# design.net
KiCad netlist of a schematic drawn in Altium Designer
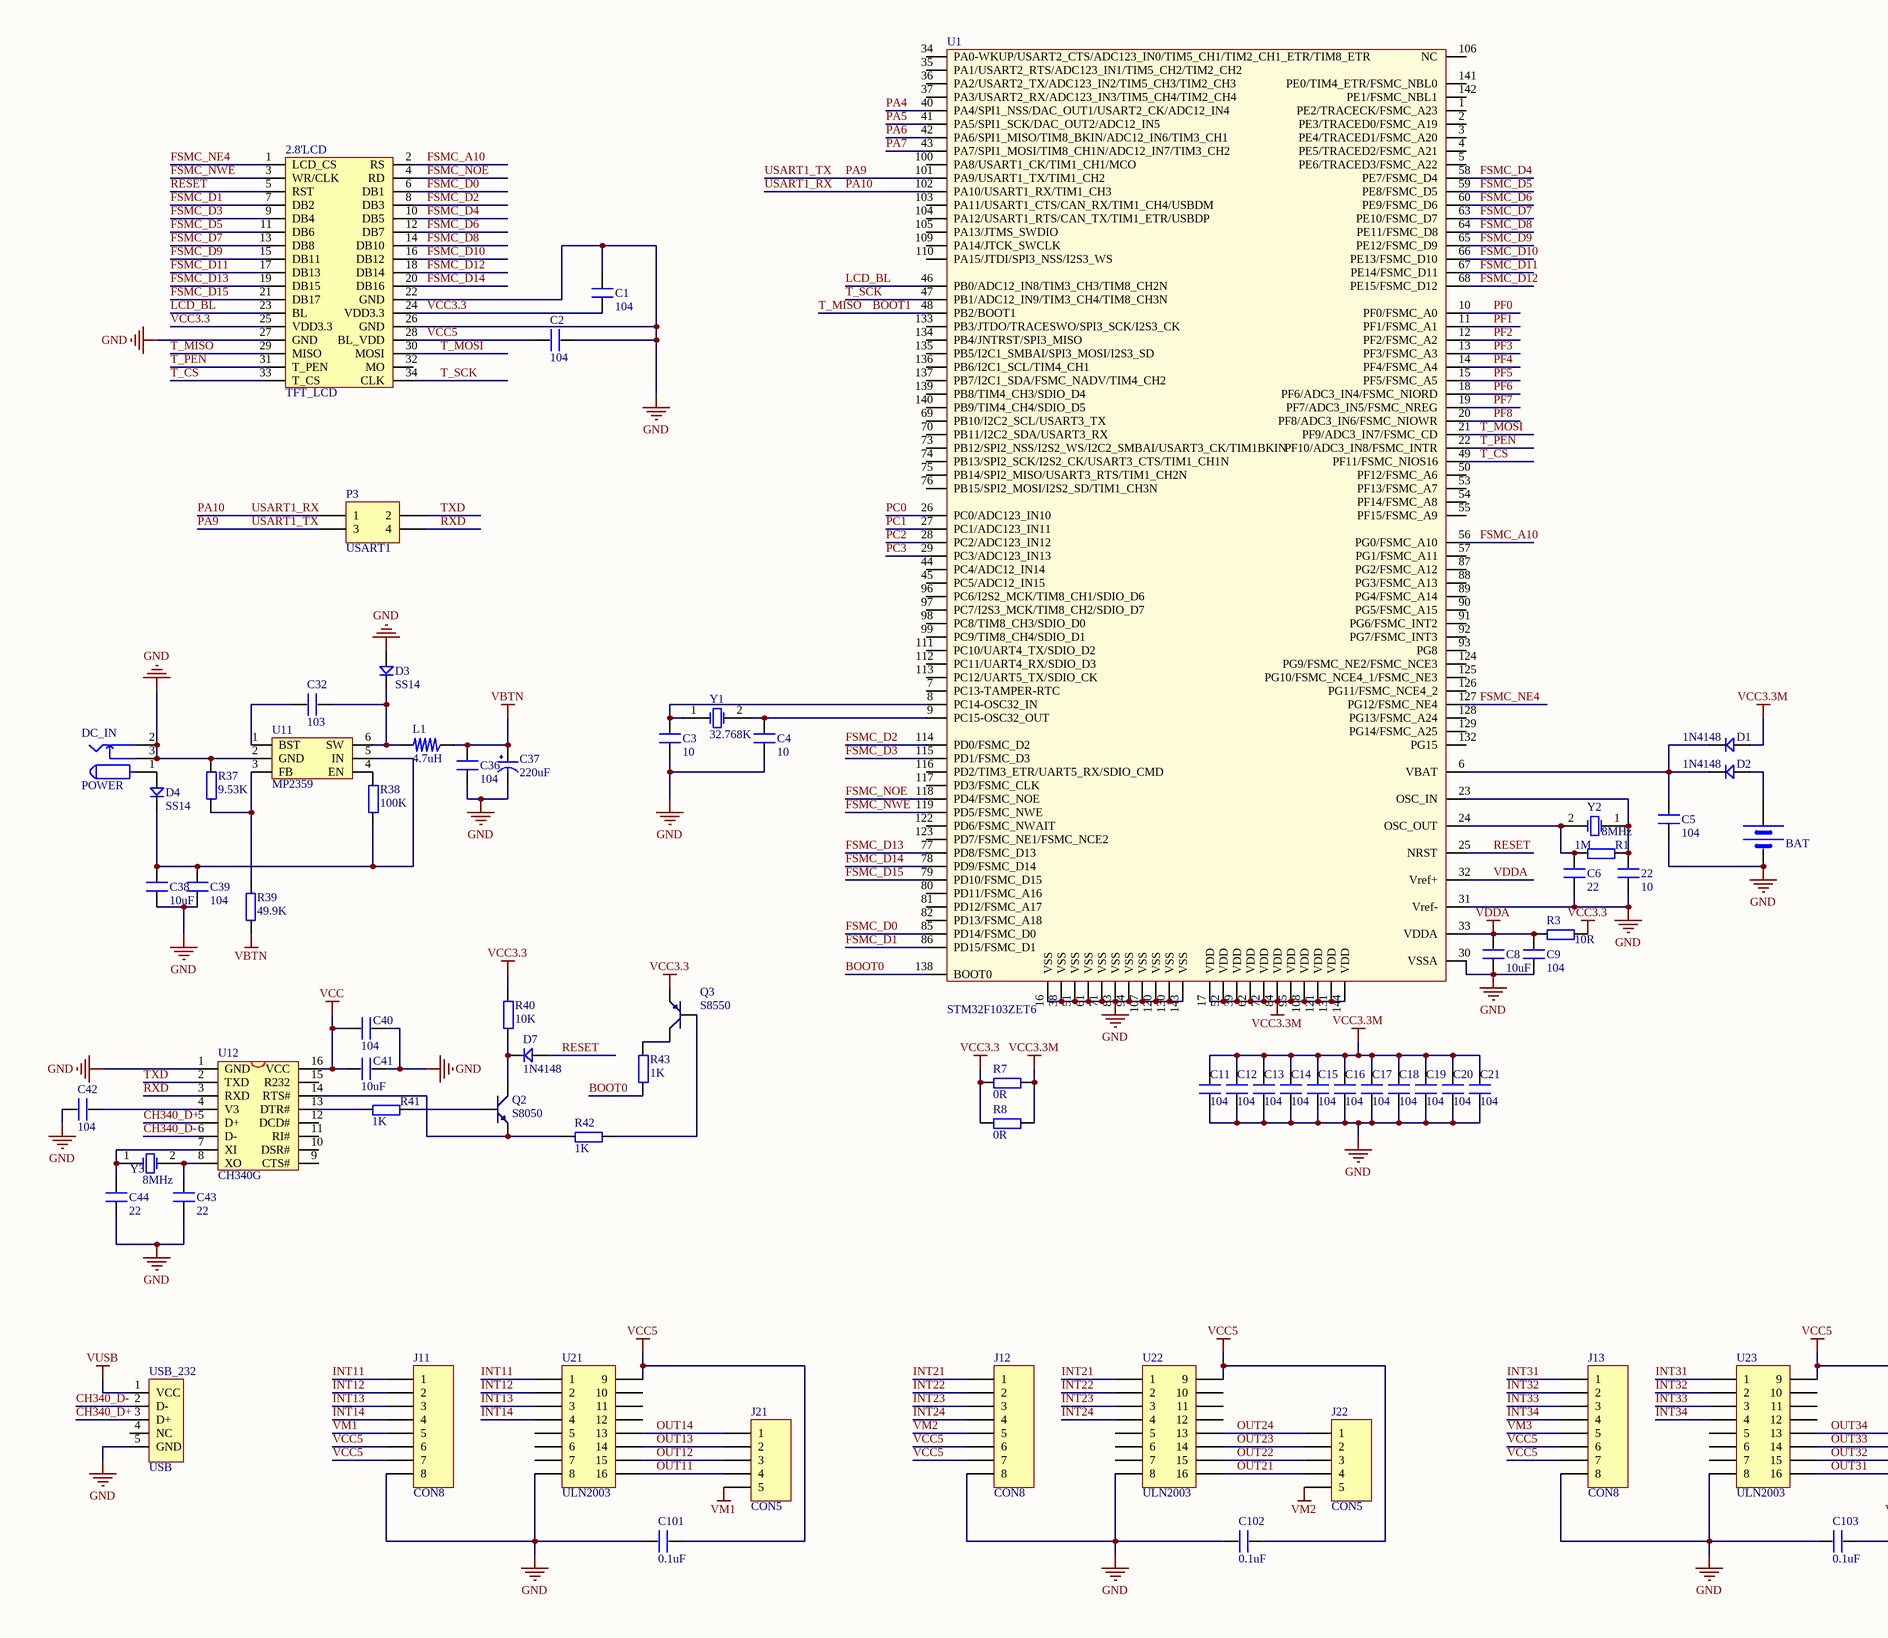
[diagram p0: 智能分类垃圾桶.SchDoc, left]
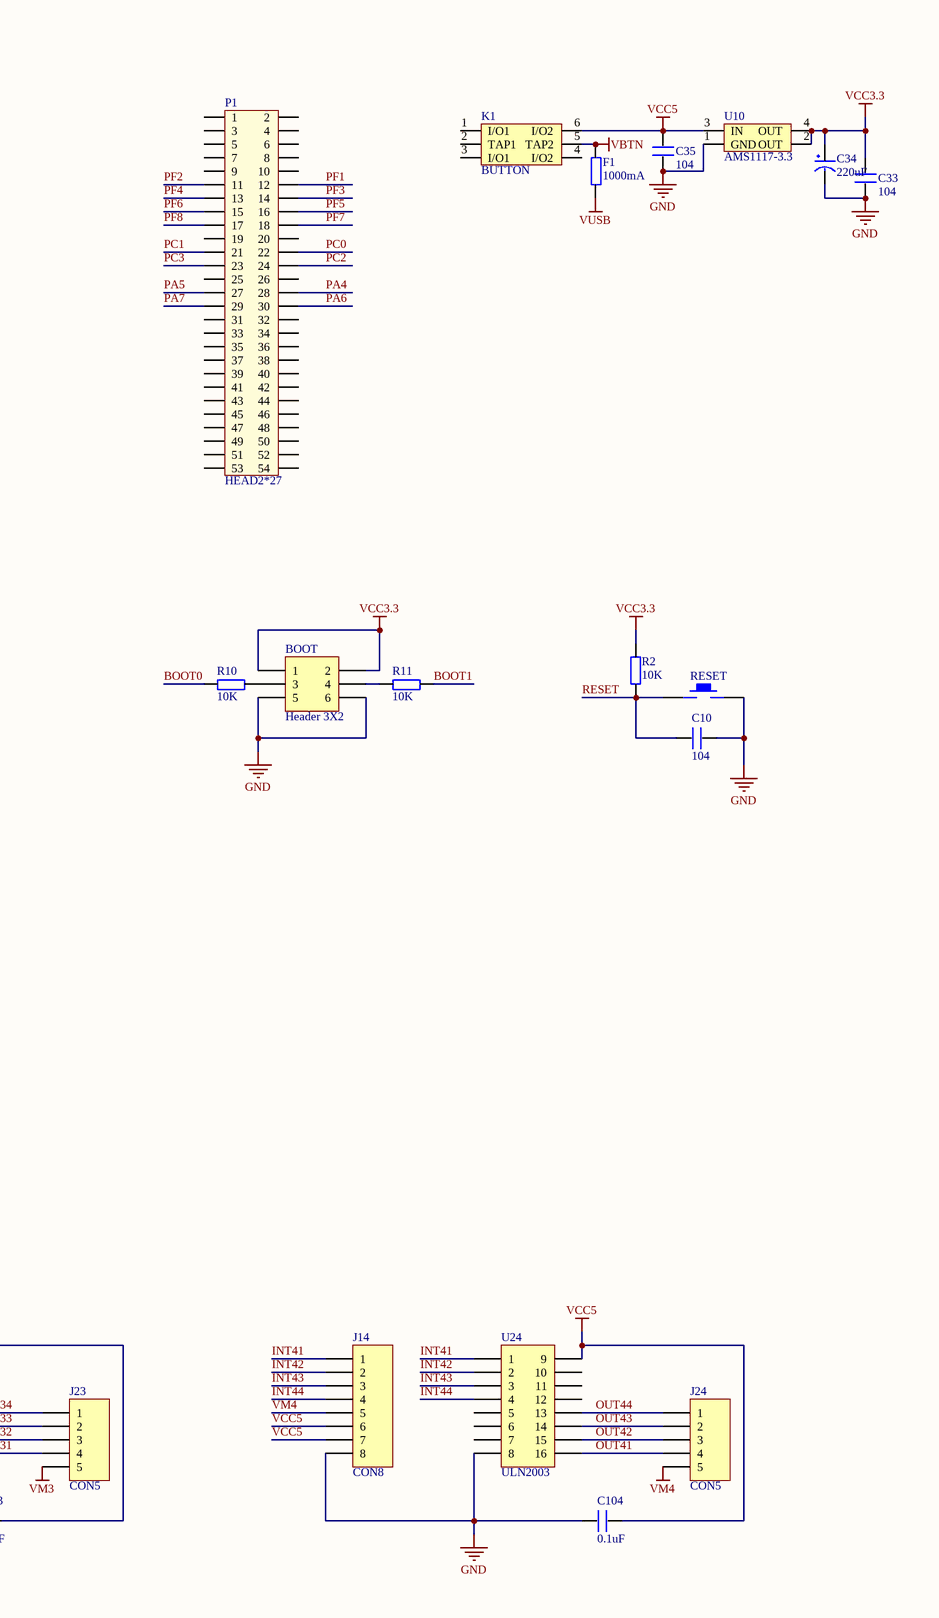
[diagram p1: 智能分类垃圾桶.SchDoc, right]

(export (version "E")
  (design (tool "Eeschema 10.0.6"))
  (components
    (comp (ref "2.8'LCD")
      (value "TFT_LCD")
      (footprint "db2*17-4.3")
      (libsource (lib "EliteSTM32封装库") (part "TFT_LCD"))
    )
    (comp (ref "22") (value "10") (footprint "0603P") (libsource (lib "EliteSTM32封装库") (part "C_1")))
    (comp (ref "BAT") (value "BATT") (footprint "BATM") (libsource (lib "EliteSTM32封装库") (part "BAT")))
    (comp (ref "BOOT")
      (value "Header 3X2")
      (footprint "HDR2X3")
      (description "Header, 3-Pin, Dual row")
      (fields (field (name "PUBLISHER") "Altium Limited"))
      (libsource (lib "EliteSTM32封装库") (part "Header 3X2"))
    )
    (comp (ref "C1") (value "104") (footprint "0603P") (libsource (lib "EliteSTM32封装库") (part "C")))
    (comp (ref "C2") (value "104") (footprint "0603P") (libsource (lib "EliteSTM32封装库") (part "C")))
    (comp (ref "C3") (value "10") (footprint "0603P") (libsource (lib "EliteSTM32封装库") (part "C_1")))
    (comp (ref "C4") (value "10") (footprint "0603P") (libsource (lib "EliteSTM32封装库") (part "C_1")))
    (comp (ref "C5") (value "104") (footprint "0603P") (libsource (lib "EliteSTM32封装库") (part "C")))
    (comp (ref "C6") (value "22") (footprint "0603P") (libsource (lib "EliteSTM32封装库") (part "C_1")))
    (comp (ref "C8") (value "10uF") (footprint "0805") (libsource (lib "EliteSTM32封装库") (part "C_2")))
    (comp (ref "C9") (value "104") (footprint "0603P") (libsource (lib "EliteSTM32封装库") (part "C")))
    (comp (ref "C10") (value "104") (footprint "0603P") (libsource (lib "EliteSTM32封装库") (part "C")))
    (comp (ref "C11") (value "104") (footprint "0603P") (libsource (lib "EliteSTM32封装库") (part "C")))
    (comp (ref "C12") (value "104") (footprint "0603P") (libsource (lib "EliteSTM32封装库") (part "C")))
    (comp (ref "C13") (value "104") (footprint "0603P") (libsource (lib "EliteSTM32封装库") (part "C")))
    (comp (ref "C14") (value "104") (footprint "0603P") (libsource (lib "EliteSTM32封装库") (part "C")))
    (comp (ref "C15") (value "104") (footprint "0603P") (libsource (lib "EliteSTM32封装库") (part "C")))
    (comp (ref "C16") (value "104") (footprint "0603P") (libsource (lib "EliteSTM32封装库") (part "C")))
    (comp (ref "C17") (value "104") (footprint "0603P") (libsource (lib "EliteSTM32封装库") (part "C")))
    (comp (ref "C18") (value "104") (footprint "0603P") (libsource (lib "EliteSTM32封装库") (part "C")))
    (comp (ref "C19") (value "104") (footprint "0603P") (libsource (lib "EliteSTM32封装库") (part "C")))
    (comp (ref "C20") (value "104") (footprint "0603P") (libsource (lib "EliteSTM32封装库") (part "C")))
    (comp (ref "C21") (value "104") (footprint "0603P") (libsource (lib "EliteSTM32封装库") (part "C")))
    (comp (ref "C32") (value "103") (footprint "0603P") (libsource (lib "EliteSTM32封装库") (part "C_3")))
    (comp (ref "C33") (value "104") (footprint "0603P") (libsource (lib "EliteSTM32封装库") (part "C")))
    (comp (ref "C34") (value "220uF") (footprint "CC6.56.5") (libsource (lib "EliteSTM32封装库") (part "CAP")))
    (comp (ref "C35") (value "104") (footprint "0603P") (libsource (lib "EliteSTM32封装库") (part "C")))
    (comp (ref "C36") (value "104") (footprint "0603P") (libsource (lib "EliteSTM32封装库") (part "C")))
    (comp (ref "C37") (value "220uF") (footprint "CC6.56.5") (libsource (lib "EliteSTM32封装库") (part "CAP")))
    (comp (ref "C38") (value "10uF") (footprint "0805") (libsource (lib "EliteSTM32封装库") (part "C_2")))
    (comp (ref "C39") (value "104") (footprint "0603P") (libsource (lib "EliteSTM32封装库") (part "C")))
    (comp (ref "C40") (value "104") (footprint "0603P") (libsource (lib "EliteSTM32封装库") (part "C")))
    (comp (ref "C41") (value "10uF") (footprint "0805") (libsource (lib "EliteSTM32封装库") (part "C_2")))
    (comp (ref "C42") (value "104") (footprint "0603P") (libsource (lib "EliteSTM32封装库") (part "C")))
    (comp (ref "C43") (value "22") (footprint "0603P") (libsource (lib "EliteSTM32封装库") (part "C_1")))
    (comp (ref "C44") (value "22") (footprint "0603P") (libsource (lib "EliteSTM32封装库") (part "C_1")))
    (comp (ref "C101") (value "0.1uF") (footprint "0805") (libsource (lib "EliteSTM32封装库") (part "C_2")))
    (comp (ref "C102") (value "0.1uF") (footprint "0805") (libsource (lib "EliteSTM32封装库") (part "C_2")))
    (comp (ref "C103") (value "0.1uF") (footprint "0805") (libsource (lib "EliteSTM32封装库") (part "C_2")))
    (comp (ref "C104") (value "0.1uF") (footprint "0805") (libsource (lib "EliteSTM32封装库") (part "C_2")))
    (comp (ref "D1") (value "1N4148") (footprint "DIODE_SOP") (libsource (lib "EliteSTM32封装库") (part "D")))
    (comp (ref "D2") (value "1N4148") (footprint "DIODE_SOP") (libsource (lib "EliteSTM32封装库") (part "D")))
    (comp (ref "D3") (value "SS14") (footprint "DIODE_SOP") (libsource (lib "EliteSTM32封装库") (part "D")))
    (comp (ref "D4") (value "SS14") (footprint "DIODE_SOP") (libsource (lib "EliteSTM32封装库") (part "D")))
    (comp (ref "D7") (value "1N4148") (footprint "DIODE_SOP") (libsource (lib "EliteSTM32封装库") (part "D")))
    (comp (ref "DC_IN") (value "POWER") (footprint "DC10B") (libsource (lib "EliteSTM32封装库") (part "POW")))
    (comp (ref "F1") (value "1000mA") (footprint "0603P") (libsource (lib "EliteSTM32封装库") (part "R")))
    (comp (ref "J11")
      (value "CON8")
      (footprint "HDR1X8")
      (description "Header, 8-Pin")
      (fields (field (name "PUBLISHER") "Altium Limited"))
      (libsource (lib "Miscellaneous Connectors") (part "Header 8"))
    )
    (comp (ref "J12")
      (value "CON8")
      (footprint "HDR1X8")
      (description "Header, 8-Pin")
      (fields (field (name "PUBLISHER") "Altium Limited"))
      (libsource (lib "Miscellaneous Connectors") (part "Header 8"))
    )
    (comp (ref "J13")
      (value "CON8")
      (footprint "HDR1X8")
      (description "Header, 8-Pin")
      (fields (field (name "PUBLISHER") "Altium Limited"))
      (libsource (lib "Miscellaneous Connectors") (part "Header 8"))
    )
    (comp (ref "J14")
      (value "CON8")
      (footprint "HDR1X8")
      (description "Header, 8-Pin")
      (fields (field (name "PUBLISHER") "Altium Limited"))
      (libsource (lib "Miscellaneous Connectors") (part "Header 8"))
    )
    (comp (ref "J21")
      (value "CON5")
      (footprint "HDR1X5")
      (description "Header, 5-Pin")
      (fields (field (name "PUBLISHER") "Altium Limited"))
      (libsource (lib "Miscellaneous Connectors") (part "Header 5"))
    )
    (comp (ref "J22")
      (value "CON5")
      (footprint "HDR1X5")
      (description "Header, 5-Pin")
      (fields (field (name "PUBLISHER") "Altium Limited"))
      (libsource (lib "Miscellaneous Connectors") (part "Header 5"))
    )
    (comp (ref "J23")
      (value "CON5")
      (footprint "HDR1X5")
      (description "Header, 5-Pin")
      (fields (field (name "PUBLISHER") "Altium Limited"))
      (libsource (lib "Miscellaneous Connectors") (part "Header 5"))
    )
    (comp (ref "J24")
      (value "CON5")
      (footprint "HDR1X5")
      (description "Header, 5-Pin")
      (fields (field (name "PUBLISHER") "Altium Limited"))
      (libsource (lib "Miscellaneous Connectors") (part "Header 5"))
    )
    (comp (ref "K1")
      (value "BUTTON")
      (footprint "BTN8.5*8.5")
      (libsource (lib "EliteSTM32封装库") (part "BUTTON"))
    )
    (comp (ref "L1") (value "4.7uH") (footprint "L_SOP74") (libsource (lib "EliteSTM32封装库") (part "L_SOP")))
    (comp (ref "P1")
      (value "HEAD2*27")
      (footprint "HEAD2*27")
      (libsource (lib "EliteSTM32封装库") (part "HEAD2*27"))
    )
    (comp (ref "P3")
      (value "USART1")
      (footprint "HDR2X2")
      (description "Header, 2-Pin, Dual row")
      (fields (field (name "PUBLISHER") "Altium Limited"))
      (libsource (lib "EliteSTM32封装库") (part "Header 2X2"))
    )
    (comp (ref "Q2")
      (value "S8050")
      (footprint "SOT-23R")
      (description "8050/BCW846/BCW847")
      (libsource (lib "EliteSTM32封装库") (part "NPN"))
    )
    (comp (ref "Q3")
      (value "S8550")
      (footprint "SOT-23R")
      (description "8550/BCW68")
      (libsource (lib "EliteSTM32封装库") (part "PNP"))
    )
    (comp (ref "R1") (value "1M") (footprint "0603P") (libsource (lib "EliteSTM32封装库") (part "R")))
    (comp (ref "R2") (value "10K") (footprint "0603P") (libsource (lib "EliteSTM32封装库") (part "R")))
    (comp (ref "R3") (value "10R") (footprint "0603P") (libsource (lib "EliteSTM32封装库") (part "R_1")))
    (comp (ref "R7") (value "0R") (footprint "0603P") (libsource (lib "EliteSTM32封装库") (part "R_2")))
    (comp (ref "R8") (value "0R") (footprint "0603P") (libsource (lib "EliteSTM32封装库") (part "R_2")))
    (comp (ref "R10") (value "10K") (footprint "0603P") (libsource (lib "EliteSTM32封装库") (part "R")))
    (comp (ref "R11") (value "10K") (footprint "0603P") (libsource (lib "EliteSTM32封装库") (part "R")))
    (comp (ref "R37") (value "9.53K") (footprint "0603P") (libsource (lib "EliteSTM32封装库") (part "R")))
    (comp (ref "R38") (value "100K") (footprint "0603P") (libsource (lib "EliteSTM32封装库") (part "R")))
    (comp (ref "R39") (value "49.9K") (footprint "0603P") (libsource (lib "EliteSTM32封装库") (part "R")))
    (comp (ref "R40") (value "10K") (footprint "0603P") (libsource (lib "EliteSTM32封装库") (part "R")))
    (comp (ref "R41") (value "1K") (footprint "0603P") (libsource (lib "EliteSTM32封装库") (part "R")))
    (comp (ref "R42") (value "1K") (footprint "0603P") (libsource (lib "EliteSTM32封装库") (part "R")))
    (comp (ref "R43") (value "1K") (footprint "0603P") (libsource (lib "EliteSTM32封装库") (part "R")))
    (comp (ref "RESET") (value "KEY_M") (footprint "KEY_M") (libsource (lib "EliteSTM32封装库") (part "KEY_M")))
    (comp (ref "U1")
      (value "STM32F103ZET6")
      (footprint "LQFP144")
      (libsource (lib "EliteSTM32封装库") (part "STM32F103ZET6"))
    )
    (comp (ref "U10")
      (value "AMS1117-3.3")
      (footprint "AMS1117")
      (libsource (lib "EliteSTM32封装库") (part "AMS1117"))
    )
    (comp (ref "U11")
      (value "MP2359")
      (footprint "SOT-23-6")
      (description "DC DC Step Down IC")
      (libsource (lib "EliteSTM32封装库") (part "MP2359"))
    )
    (comp (ref "U12")
      (value "CH340G")
      (footprint "SOP16M")
      (description "USB2UART")
      (libsource (lib "EliteSTM32封装库") (part "CH340G"))
    )
    (comp (ref "U21")
      (value "ULN2003")
      (footprint "SOP16M")
      (description "Header, 8-Pin, Dual row")
      (fields (field (name "PUBLISHER") "Altium Limited"))
      (libsource (lib "Miscellaneous Connectors") (part "Header 8X2A"))
    )
    (comp (ref "U22")
      (value "ULN2003")
      (footprint "SOP16M")
      (description "Header, 8-Pin, Dual row")
      (fields (field (name "PUBLISHER") "Altium Limited"))
      (libsource (lib "Miscellaneous Connectors") (part "Header 8X2A"))
    )
    (comp (ref "U23")
      (value "ULN2003")
      (footprint "SOP16M")
      (description "Header, 8-Pin, Dual row")
      (fields (field (name "PUBLISHER") "Altium Limited"))
      (libsource (lib "Miscellaneous Connectors") (part "Header 8X2A"))
    )
    (comp (ref "U24")
      (value "ULN2003")
      (footprint "SOP16M")
      (description "Header, 8-Pin, Dual row")
      (fields (field (name "PUBLISHER") "Altium Limited"))
      (libsource (lib "Miscellaneous Connectors") (part "Header 8X2A"))
    )
    (comp (ref "USB_232")
      (value "USB")
      (footprint "USB/SM0.8-6H5")
      (libsource (lib "EliteSTM32封装库") (part "USB5"))
    )
    (comp (ref "Y1")
      (value "32.768K")
      (footprint "XTAL32")
      (description "Crystal Oscillator")
      (fields (field (name "PUBLISHER") "Altium Limited"))
      (libsource (lib "EliteSTM32封装库") (part "XTAL_1"))
    )
    (comp (ref "Y2")
      (value "8MHz")
      (footprint "XTAL_US")
      (description "Crystal Oscillator")
      (fields (field (name "PUBLISHER") "Altium Limited"))
      (libsource (lib "EliteSTM32封装库") (part "XTAL"))
    )
    (comp (ref "Y3")
      (value "8MHz")
      (footprint "XTAL_US")
      (description "Crystal Oscillator")
      (fields (field (name "PUBLISHER") "Altium Limited"))
      (libsource (lib "EliteSTM32封装库") (part "XTAL"))
    )
  )
  (nets
    (net (code "1") (name "/BOOT0") (class "Default")
      (node (ref "R10") (pin "1") (pintype "passive"))
      (node (ref "R43") (pin "1") (pintype "passive"))
      (node (ref "U1") (pin "138") (pinfunction "BOOT0_138") (pintype "passive"))
    )
    (net (code "2") (name "/BOOT1") (class "Default")
      (node (ref "2.8'LCD") (pin "29") (pinfunction "MISO_29") (pintype "passive"))
      (node (ref "R11") (pin "2") (pintype "passive"))
      (node (ref "U1") (pin "48") (pinfunction "PB2/BOOT1_48") (pintype "passive"))
    )
    (net (code "3") (name "/CH340_D+") (class "Default")
      (node (ref "U12") (pin "5") (pinfunction "D+_5") (pintype "passive"))
      (node (ref "USB_232") (pin "3") (pinfunction "D+_3") (pintype "passive"))
    )
    (net (code "4") (name "/CH340_D-") (class "Default")
      (node (ref "U12") (pin "6") (pinfunction "D-_6") (pintype "passive"))
      (node (ref "USB_232") (pin "2") (pinfunction "D-_2") (pintype "passive"))
    )
    (net (code "5") (name "/FSMC_A10") (class "Default")
      (node (ref "2.8'LCD") (pin "2") (pinfunction "RS_2") (pintype "passive"))
      (node (ref "U1") (pin "56") (pinfunction "PG0/FSMC_A10_56") (pintype "passive"))
    )
    (net (code "6") (name "/FSMC_D0") (class "Default")
      (node (ref "2.8'LCD") (pin "6") (pinfunction "DB1_6") (pintype "passive"))
      (node (ref "U1") (pin "85") (pinfunction "PD14/FSMC_D0_85") (pintype "passive"))
    )
    (net (code "7") (name "/FSMC_D1") (class "Default")
      (node (ref "2.8'LCD") (pin "7") (pinfunction "DB2_7") (pintype "passive"))
      (node (ref "U1") (pin "86") (pinfunction "PD15/FSMC_D1_86") (pintype "passive"))
    )
    (net (code "8") (name "/FSMC_D2") (class "Default")
      (node (ref "2.8'LCD") (pin "8") (pinfunction "DB3_8") (pintype "passive"))
      (node (ref "U1") (pin "114") (pinfunction "PD0/FSMC_D2_114") (pintype "passive"))
    )
    (net (code "9") (name "/FSMC_D3") (class "Default")
      (node (ref "2.8'LCD") (pin "9") (pinfunction "DB4_9") (pintype "passive"))
      (node (ref "U1") (pin "115") (pinfunction "PD1/FSMC_D3_115") (pintype "passive"))
    )
    (net (code "10") (name "/FSMC_D4") (class "Default")
      (node (ref "2.8'LCD") (pin "10") (pinfunction "DB5_10") (pintype "passive"))
      (node (ref "U1") (pin "58") (pinfunction "PE7/FSMC_D4_58") (pintype "passive"))
    )
    (net (code "11") (name "/FSMC_D5") (class "Default")
      (node (ref "2.8'LCD") (pin "11") (pinfunction "DB6_11") (pintype "passive"))
      (node (ref "U1") (pin "59") (pinfunction "PE8/FSMC_D5_59") (pintype "passive"))
    )
    (net (code "12") (name "/FSMC_D6") (class "Default")
      (node (ref "2.8'LCD") (pin "12") (pinfunction "DB7_12") (pintype "passive"))
      (node (ref "U1") (pin "60") (pinfunction "PE9/FSMC_D6_60") (pintype "passive"))
    )
    (net (code "13") (name "/FSMC_D7") (class "Default")
      (node (ref "2.8'LCD") (pin "13") (pinfunction "DB8_13") (pintype "passive"))
      (node (ref "U1") (pin "63") (pinfunction "PE10/FSMC_D7_63") (pintype "passive"))
    )
    (net (code "14") (name "/FSMC_D8") (class "Default")
      (node (ref "2.8'LCD") (pin "14") (pinfunction "DB10_14") (pintype "passive"))
      (node (ref "U1") (pin "64") (pinfunction "PE11/FSMC_D8_64") (pintype "passive"))
    )
    (net (code "15") (name "/FSMC_D9") (class "Default")
      (node (ref "2.8'LCD") (pin "15") (pinfunction "DB11_15") (pintype "passive"))
      (node (ref "U1") (pin "65") (pinfunction "PE12/FSMC_D9_65") (pintype "passive"))
    )
    (net (code "16") (name "/FSMC_D10") (class "Default")
      (node (ref "2.8'LCD") (pin "16") (pinfunction "DB12_16") (pintype "passive"))
      (node (ref "U1") (pin "66") (pinfunction "PE13/FSMC_D10_66") (pintype "passive"))
    )
    (net (code "17") (name "/FSMC_D11") (class "Default")
      (node (ref "2.8'LCD") (pin "17") (pinfunction "DB13_17") (pintype "passive"))
      (node (ref "U1") (pin "67") (pinfunction "PE14/FSMC_D11_67") (pintype "passive"))
    )
    (net (code "18") (name "/FSMC_D12") (class "Default")
      (node (ref "2.8'LCD") (pin "18") (pinfunction "DB14_18") (pintype "passive"))
      (node (ref "U1") (pin "68") (pinfunction "PE15/FSMC_D12_68") (pintype "passive"))
    )
    (net (code "19") (name "/FSMC_D13") (class "Default")
      (node (ref "2.8'LCD") (pin "19") (pinfunction "DB15_19") (pintype "passive"))
      (node (ref "U1") (pin "77") (pinfunction "PD8/FSMC_D13_77") (pintype "passive"))
    )
    (net (code "20") (name "/FSMC_D14") (class "Default")
      (node (ref "2.8'LCD") (pin "20") (pinfunction "DB16_20") (pintype "passive"))
      (node (ref "U1") (pin "78") (pinfunction "PD9/FSMC_D14_78") (pintype "passive"))
    )
    (net (code "21") (name "/FSMC_D15") (class "Default")
      (node (ref "2.8'LCD") (pin "21") (pinfunction "DB17_21") (pintype "passive"))
      (node (ref "U1") (pin "79") (pinfunction "PD10/FSMC_D15_79") (pintype "passive"))
    )
    (net (code "22") (name "/FSMC_NE4") (class "Default")
      (node (ref "2.8'LCD") (pin "1") (pinfunction "LCD_CS_1") (pintype "passive"))
      (node (ref "U1") (pin "127") (pinfunction "PG12/FSMC_NE4_127") (pintype "passive"))
    )
    (net (code "23") (name "/FSMC_NOE") (class "Default")
      (node (ref "2.8'LCD") (pin "4") (pinfunction "RD_4") (pintype "passive"))
      (node (ref "U1") (pin "118") (pinfunction "PD4/FSMC_NOE_118") (pintype "passive"))
    )
    (net (code "24") (name "/FSMC_NWE") (class "Default")
      (node (ref "2.8'LCD") (pin "3") (pinfunction "WR/CLK_3") (pintype "passive"))
      (node (ref "U1") (pin "119") (pinfunction "PD5/FSMC_NWE_119") (pintype "passive"))
    )
    (net (code "25") (name "/INT11") (class "Default")
      (node (ref "J11") (pin "1") (pinfunction "1_1") (pintype "passive"))
      (node (ref "U21") (pin "1") (pinfunction "1_1") (pintype "passive"))
    )
    (net (code "26") (name "/INT12") (class "Default")
      (node (ref "J11") (pin "2") (pinfunction "2_2") (pintype "passive"))
      (node (ref "U21") (pin "2") (pinfunction "2_2") (pintype "passive"))
    )
    (net (code "27") (name "/INT13") (class "Default")
      (node (ref "J11") (pin "3") (pinfunction "3_3") (pintype "passive"))
      (node (ref "U21") (pin "3") (pinfunction "3_3") (pintype "passive"))
    )
    (net (code "28") (name "/INT14") (class "Default")
      (node (ref "J11") (pin "4") (pinfunction "4_4") (pintype "passive"))
      (node (ref "U21") (pin "4") (pinfunction "4_4") (pintype "passive"))
    )
    (net (code "29") (name "/INT21") (class "Default")
      (node (ref "J12") (pin "1") (pinfunction "1_1") (pintype "passive"))
      (node (ref "U22") (pin "1") (pinfunction "1_1") (pintype "passive"))
    )
    (net (code "30") (name "/INT22") (class "Default")
      (node (ref "J12") (pin "2") (pinfunction "2_2") (pintype "passive"))
      (node (ref "U22") (pin "2") (pinfunction "2_2") (pintype "passive"))
    )
    (net (code "31") (name "/INT23") (class "Default")
      (node (ref "J12") (pin "3") (pinfunction "3_3") (pintype "passive"))
      (node (ref "U22") (pin "3") (pinfunction "3_3") (pintype "passive"))
    )
    (net (code "32") (name "/INT24") (class "Default")
      (node (ref "J12") (pin "4") (pinfunction "4_4") (pintype "passive"))
      (node (ref "U22") (pin "4") (pinfunction "4_4") (pintype "passive"))
    )
    (net (code "33") (name "/INT31") (class "Default")
      (node (ref "J13") (pin "1") (pinfunction "1_1") (pintype "passive"))
      (node (ref "U23") (pin "1") (pinfunction "1_1") (pintype "passive"))
    )
    (net (code "34") (name "/INT32") (class "Default")
      (node (ref "J13") (pin "2") (pinfunction "2_2") (pintype "passive"))
      (node (ref "U23") (pin "2") (pinfunction "2_2") (pintype "passive"))
    )
    (net (code "35") (name "/INT33") (class "Default")
      (node (ref "J13") (pin "3") (pinfunction "3_3") (pintype "passive"))
      (node (ref "U23") (pin "3") (pinfunction "3_3") (pintype "passive"))
    )
    (net (code "36") (name "/INT34") (class "Default")
      (node (ref "J13") (pin "4") (pinfunction "4_4") (pintype "passive"))
      (node (ref "U23") (pin "4") (pinfunction "4_4") (pintype "passive"))
    )
    (net (code "37") (name "/INT41") (class "Default")
      (node (ref "J14") (pin "1") (pinfunction "1_1") (pintype "passive"))
      (node (ref "U24") (pin "1") (pinfunction "1_1") (pintype "passive"))
    )
    (net (code "38") (name "/INT42") (class "Default")
      (node (ref "J14") (pin "2") (pinfunction "2_2") (pintype "passive"))
      (node (ref "U24") (pin "2") (pinfunction "2_2") (pintype "passive"))
    )
    (net (code "39") (name "/INT43") (class "Default")
      (node (ref "J14") (pin "3") (pinfunction "3_3") (pintype "passive"))
      (node (ref "U24") (pin "3") (pinfunction "3_3") (pintype "passive"))
    )
    (net (code "40") (name "/INT44") (class "Default")
      (node (ref "J14") (pin "4") (pinfunction "4_4") (pintype "passive"))
      (node (ref "U24") (pin "4") (pinfunction "4_4") (pintype "passive"))
    )
    (net (code "41") (name "/LCD_BL") (class "Default")
      (node (ref "2.8'LCD") (pin "23") (pinfunction "BL_23") (pintype "passive"))
      (node (ref "U1") (pin "46") (pinfunction "PB0/ADC12_IN8/TIM3_CH3/TIM8_CH2N_46") (pintype "passive"))
    )
    (net (code "42") (name "/OUT11") (class "Default")
      (node (ref "J21") (pin "4") (pinfunction "4_4") (pintype "passive"))
      (node (ref "U21") (pin "16") (pinfunction "16_16") (pintype "passive"))
    )
    (net (code "43") (name "/OUT12") (class "Default")
      (node (ref "J21") (pin "3") (pinfunction "3_3") (pintype "passive"))
      (node (ref "U21") (pin "15") (pinfunction "15_15") (pintype "passive"))
    )
    (net (code "44") (name "/OUT13") (class "Default")
      (node (ref "J21") (pin "2") (pinfunction "2_2") (pintype "passive"))
      (node (ref "U21") (pin "14") (pinfunction "14_14") (pintype "passive"))
    )
    (net (code "45") (name "/OUT14") (class "Default")
      (node (ref "J21") (pin "1") (pinfunction "1_1") (pintype "passive"))
      (node (ref "U21") (pin "13") (pinfunction "13_13") (pintype "passive"))
    )
    (net (code "46") (name "/OUT21") (class "Default")
      (node (ref "J22") (pin "4") (pinfunction "4_4") (pintype "passive"))
      (node (ref "U22") (pin "16") (pinfunction "16_16") (pintype "passive"))
    )
    (net (code "47") (name "/OUT22") (class "Default")
      (node (ref "J22") (pin "3") (pinfunction "3_3") (pintype "passive"))
      (node (ref "U22") (pin "15") (pinfunction "15_15") (pintype "passive"))
    )
    (net (code "48") (name "/OUT23") (class "Default")
      (node (ref "J22") (pin "2") (pinfunction "2_2") (pintype "passive"))
      (node (ref "U22") (pin "14") (pinfunction "14_14") (pintype "passive"))
    )
    (net (code "49") (name "/OUT24") (class "Default")
      (node (ref "J22") (pin "1") (pinfunction "1_1") (pintype "passive"))
      (node (ref "U22") (pin "13") (pinfunction "13_13") (pintype "passive"))
    )
    (net (code "50") (name "/OUT31") (class "Default")
      (node (ref "J23") (pin "4") (pinfunction "4_4") (pintype "passive"))
      (node (ref "U23") (pin "16") (pinfunction "16_16") (pintype "passive"))
    )
    (net (code "51") (name "/OUT32") (class "Default")
      (node (ref "J23") (pin "3") (pinfunction "3_3") (pintype "passive"))
      (node (ref "U23") (pin "15") (pinfunction "15_15") (pintype "passive"))
    )
    (net (code "52") (name "/OUT33") (class "Default")
      (node (ref "J23") (pin "2") (pinfunction "2_2") (pintype "passive"))
      (node (ref "U23") (pin "14") (pinfunction "14_14") (pintype "passive"))
    )
    (net (code "53") (name "/OUT34") (class "Default")
      (node (ref "J23") (pin "1") (pinfunction "1_1") (pintype "passive"))
      (node (ref "U23") (pin "13") (pinfunction "13_13") (pintype "passive"))
    )
    (net (code "54") (name "/OUT41") (class "Default")
      (node (ref "J24") (pin "4") (pinfunction "4_4") (pintype "passive"))
      (node (ref "U24") (pin "16") (pinfunction "16_16") (pintype "passive"))
    )
    (net (code "55") (name "/OUT42") (class "Default")
      (node (ref "J24") (pin "3") (pinfunction "3_3") (pintype "passive"))
      (node (ref "U24") (pin "15") (pinfunction "15_15") (pintype "passive"))
    )
    (net (code "56") (name "/OUT43") (class "Default")
      (node (ref "J24") (pin "2") (pinfunction "2_2") (pintype "passive"))
      (node (ref "U24") (pin "14") (pinfunction "14_14") (pintype "passive"))
    )
    (net (code "57") (name "/OUT44") (class "Default")
      (node (ref "J24") (pin "1") (pinfunction "1_1") (pintype "passive"))
      (node (ref "U24") (pin "13") (pinfunction "13_13") (pintype "passive"))
    )
    (net (code "58") (name "/PA4") (class "Default")
      (node (ref "P1") (pin "28") (pinfunction "28_28") (pintype "passive"))
      (node (ref "U1") (pin "40") (pinfunction "PA4/SPI1_NSS/DAC_OUT1/USART2_CK/ADC12_IN4_40") (pintype "passive"))
    )
    (net (code "59") (name "/PA5") (class "Default")
      (node (ref "P1") (pin "27") (pinfunction "27_27") (pintype "passive"))
      (node (ref "U1") (pin "41") (pinfunction "PA5/SPI1_SCK/DAC_OUT2/ADC12_IN5_41") (pintype "passive"))
    )
    (net (code "60") (name "/PA6") (class "Default")
      (node (ref "P1") (pin "30") (pinfunction "30_30") (pintype "passive"))
      (node (ref "U1") (pin "42") (pinfunction "PA6/SPI1_MISO/TIM8_BKIN/ADC12_IN6/TIM3_CH1_42") (pintype "passive"))
    )
    (net (code "61") (name "/PA7") (class "Default")
      (node (ref "P1") (pin "29") (pinfunction "29_29") (pintype "passive"))
      (node (ref "U1") (pin "43") (pinfunction "PA7/SPI1_MOSI/TIM8_CH1N/ADC12_IN7/TIM3_CH2_43") (pintype "passive"))
    )
    (net (code "62") (name "/PA9") (class "Default")
      (node (ref "P3") (pin "3") (pinfunction "3_3") (pintype "passive"))
      (node (ref "U1") (pin "101") (pinfunction "PA9/USART1_TX/TIM1_CH2_101") (pintype "passive"))
    )
    (net (code "63") (name "/PA10") (class "Default")
      (node (ref "P3") (pin "1") (pinfunction "1_1") (pintype "passive"))
      (node (ref "U1") (pin "102") (pinfunction "PA10/USART1_RX/TIM1_CH3_102") (pintype "passive"))
    )
    (net (code "64") (name "/PC0") (class "Default")
      (node (ref "P1") (pin "22") (pinfunction "22_22") (pintype "passive"))
      (node (ref "U1") (pin "26") (pinfunction "PC0/ADC123_IN10_26") (pintype "passive"))
    )
    (net (code "65") (name "/PC1") (class "Default")
      (node (ref "P1") (pin "21") (pinfunction "21_21") (pintype "passive"))
      (node (ref "U1") (pin "27") (pinfunction "PC1/ADC123_IN11_27") (pintype "passive"))
    )
    (net (code "66") (name "/PC2") (class "Default")
      (node (ref "P1") (pin "24") (pinfunction "24_24") (pintype "passive"))
      (node (ref "U1") (pin "28") (pinfunction "PC2/ADC123_IN12_28") (pintype "passive"))
    )
    (net (code "67") (name "/PC3") (class "Default")
      (node (ref "P1") (pin "23") (pinfunction "23_23") (pintype "passive"))
      (node (ref "U1") (pin "29") (pinfunction "PC3/ADC123_IN13_29") (pintype "passive"))
    )
    (net (code "68") (name "/PF0") (class "Default")
      (node (ref "U1") (pin "10") (pinfunction "PF0/FSMC_A0_10") (pintype "passive"))
    )
    (net (code "69") (name "/PF1") (class "Default")
      (node (ref "P1") (pin "12") (pinfunction "12_12") (pintype "passive"))
      (node (ref "U1") (pin "11") (pinfunction "PF1/FSMC_A1_11") (pintype "passive"))
    )
    (net (code "70") (name "/PF2") (class "Default")
      (node (ref "P1") (pin "11") (pinfunction "11_11") (pintype "passive"))
      (node (ref "U1") (pin "12") (pinfunction "PF2/FSMC_A2_12") (pintype "passive"))
    )
    (net (code "71") (name "/PF3") (class "Default")
      (node (ref "P1") (pin "14") (pinfunction "14_14") (pintype "passive"))
      (node (ref "U1") (pin "13") (pinfunction "PF3/FSMC_A3_13") (pintype "passive"))
    )
    (net (code "72") (name "/PF4") (class "Default")
      (node (ref "P1") (pin "13") (pinfunction "13_13") (pintype "passive"))
      (node (ref "U1") (pin "14") (pinfunction "PF4/FSMC_A4_14") (pintype "passive"))
    )
    (net (code "73") (name "/PF5") (class "Default")
      (node (ref "P1") (pin "16") (pinfunction "16_16") (pintype "passive"))
      (node (ref "U1") (pin "15") (pinfunction "PF5/FSMC_A5_15") (pintype "passive"))
    )
    (net (code "74") (name "/PF6") (class "Default")
      (node (ref "P1") (pin "15") (pinfunction "15_15") (pintype "passive"))
      (node (ref "U1") (pin "18") (pinfunction "PF6/ADC3_IN4/FSMC_NIORD_18") (pintype "passive"))
    )
    (net (code "75") (name "/PF7") (class "Default")
      (node (ref "P1") (pin "18") (pinfunction "18_18") (pintype "passive"))
      (node (ref "U1") (pin "19") (pinfunction "PF7/ADC3_IN5/FSMC_NREG_19") (pintype "passive"))
    )
    (net (code "76") (name "/PF8") (class "Default")
      (node (ref "P1") (pin "17") (pinfunction "17_17") (pintype "passive"))
      (node (ref "U1") (pin "20") (pinfunction "PF8/ADC3_IN6/FSMC_NIOWR_20") (pintype "passive"))
    )
    (net (code "77") (name "/RESET") (class "Default")
      (node (ref "2.8'LCD") (pin "5") (pinfunction "RST_5") (pintype "passive"))
      (node (ref "C10") (pin "1") (pintype "passive"))
      (node (ref "D7") (pin "1") (pintype "passive"))
      (node (ref "R2") (pin "2") (pintype "passive"))
      (node (ref "RESET") (pin "1") (pinfunction "1_1") (pintype "passive"))
      (node (ref "U1") (pin "25") (pinfunction "NRST_25") (pintype "passive"))
    )
    (net (code "78") (name "/RXD") (class "Default")
      (node (ref "P3") (pin "4") (pinfunction "4_4") (pintype "passive"))
      (node (ref "U12") (pin "3") (pinfunction "RXD_3") (pintype "passive"))
    )
    (net (code "79") (name "/TXD") (class "Default")
      (node (ref "P3") (pin "2") (pinfunction "2_2") (pintype "passive"))
      (node (ref "U12") (pin "2") (pinfunction "TXD_2") (pintype "passive"))
    )
    (net (code "80") (name "/T_CS") (class "Default")
      (node (ref "2.8'LCD") (pin "33") (pinfunction "T_CS_33") (pintype "passive"))
      (node (ref "U1") (pin "49") (pinfunction "PF11/FSMC_NIOS16_49") (pintype "passive"))
    )
    (net (code "81") (name "/T_MOSI") (class "Default")
      (node (ref "2.8'LCD") (pin "30") (pinfunction "MOSI_30") (pintype "passive"))
      (node (ref "U1") (pin "21") (pinfunction "PF9/ADC3_IN7/FSMC_CD_21") (pintype "passive"))
    )
    (net (code "82") (name "/T_PEN") (class "Default")
      (node (ref "2.8'LCD") (pin "31") (pinfunction "T_PEN_31") (pintype "passive"))
      (node (ref "U1") (pin "22") (pinfunction "PF10/ADC3_IN8/FSMC_INTR_22") (pintype "passive"))
    )
    (net (code "83") (name "/T_SCK") (class "Default")
      (node (ref "2.8'LCD") (pin "34") (pinfunction "CLK_34") (pintype "passive"))
      (node (ref "U1") (pin "47") (pinfunction "PB1/ADC12_IN9/TIM3_CH4/TIM8_CH3N_47") (pintype "passive"))
    )
    (net (code "84") (name "GND") (class "Default")
      (node (ref "2.8'LCD") (pin "22") (pinfunction "GND_22") (pintype "passive"))
      (node (ref "2.8'LCD") (pin "26") (pinfunction "GND_26") (pintype "passive"))
      (node (ref "2.8'LCD") (pin "27") (pinfunction "GND_27") (pintype "passive"))
      (node (ref "22") (pin "1") (pintype "passive"))
      (node (ref "BAT") (pin "2") (pinfunction "GND_2") (pintype "passive"))
      (node (ref "BOOT") (pin "5") (pinfunction "5_5") (pintype "passive"))
      (node (ref "BOOT") (pin "6") (pinfunction "6_6") (pintype "passive"))
      (node (ref "C1") (pin "2") (pintype "passive"))
      (node (ref "C10") (pin "2") (pintype "passive"))
      (node (ref "C101") (pin "1") (pintype "passive"))
      (node (ref "C102") (pin "1") (pintype "passive"))
      (node (ref "C103") (pin "1") (pintype "passive"))
      (node (ref "C104") (pin "1") (pintype "passive"))
      (node (ref "C11") (pin "1") (pintype "passive"))
      (node (ref "C12") (pin "1") (pintype "passive"))
      (node (ref "C13") (pin "1") (pintype "passive"))
      (node (ref "C14") (pin "1") (pintype "passive"))
      (node (ref "C15") (pin "1") (pintype "passive"))
      (node (ref "C16") (pin "1") (pintype "passive"))
      (node (ref "C17") (pin "1") (pintype "passive"))
      (node (ref "C18") (pin "1") (pintype "passive"))
      (node (ref "C19") (pin "1") (pintype "passive"))
      (node (ref "C2") (pin "2") (pintype "passive"))
      (node (ref "C20") (pin "1") (pintype "passive"))
      (node (ref "C21") (pin "1") (pintype "passive"))
      (node (ref "C3") (pin "1") (pintype "passive"))
      (node (ref "C33") (pin "1") (pintype "passive"))
      (node (ref "C34") (pin "2") (pinfunction "GND_2") (pintype "passive"))
      (node (ref "C35") (pin "1") (pintype "passive"))
      (node (ref "C36") (pin "1") (pintype "passive"))
      (node (ref "C37") (pin "2") (pinfunction "GND_2") (pintype "passive"))
      (node (ref "C38") (pin "2") (pintype "passive"))
      (node (ref "C39") (pin "2") (pintype "passive"))
      (node (ref "C4") (pin "1") (pintype "passive"))
      (node (ref "C40") (pin "2") (pintype "passive"))
      (node (ref "C41") (pin "2") (pintype "passive"))
      (node (ref "C42") (pin "1") (pintype "passive"))
      (node (ref "C43") (pin "1") (pintype "passive"))
      (node (ref "C44") (pin "1") (pintype "passive"))
      (node (ref "C5") (pin "1") (pintype "passive"))
      (node (ref "C6") (pin "1") (pintype "passive"))
      (node (ref "C8") (pin "1") (pintype "passive"))
      (node (ref "C9") (pin "1") (pintype "passive"))
      (node (ref "D3") (pin "1") (pintype "passive"))
      (node (ref "DC_IN") (pin "2") (pintype "passive"))
      (node (ref "DC_IN") (pin "3") (pintype "passive"))
      (node (ref "J11") (pin "8") (pinfunction "8_8") (pintype "passive"))
      (node (ref "J12") (pin "8") (pinfunction "8_8") (pintype "passive"))
      (node (ref "J13") (pin "8") (pinfunction "8_8") (pintype "passive"))
      (node (ref "J14") (pin "8") (pinfunction "8_8") (pintype "passive"))
      (node (ref "R37") (pin "2") (pintype "passive"))
      (node (ref "RESET") (pin "2") (pinfunction "2_2") (pintype "passive"))
      (node (ref "U1") (pin "107") (pinfunction "VSS_107") (pintype "passive"))
      (node (ref "U1") (pin "120") (pinfunction "VSS_120") (pintype "passive"))
      (node (ref "U1") (pin "130") (pinfunction "VSS_130") (pintype "passive"))
      (node (ref "U1") (pin "143") (pinfunction "VSS_143") (pintype "passive"))
      (node (ref "U1") (pin "16") (pinfunction "VSS_16") (pintype "passive"))
      (node (ref "U1") (pin "30") (pinfunction "VSSA_30") (pintype "passive"))
      (node (ref "U1") (pin "31") (pinfunction "Vref-_31") (pintype "passive"))
      (node (ref "U1") (pin "38") (pinfunction "VSS_38") (pintype "passive"))
      (node (ref "U1") (pin "51") (pinfunction "VSS_51") (pintype "passive"))
      (node (ref "U1") (pin "61") (pinfunction "VSS_61") (pintype "passive"))
      (node (ref "U1") (pin "71") (pinfunction "VSS_71") (pintype "passive"))
      (node (ref "U1") (pin "83") (pinfunction "VSS_83") (pintype "passive"))
      (node (ref "U1") (pin "94") (pinfunction "VSS_94") (pintype "passive"))
      (node (ref "U10") (pin "1") (pinfunction "GND_1") (pintype "passive"))
      (node (ref "U11") (pin "2") (pinfunction "GND_2") (pintype "passive"))
      (node (ref "U12") (pin "1") (pinfunction "GND_1") (pintype "passive"))
      (node (ref "U21") (pin "8") (pinfunction "8_8") (pintype "passive"))
      (node (ref "U22") (pin "8") (pinfunction "8_8") (pintype "passive"))
      (node (ref "U23") (pin "8") (pinfunction "8_8") (pintype "passive"))
      (node (ref "U24") (pin "8") (pinfunction "8_8") (pintype "passive"))
      (node (ref "USB_232") (pin "5") (pinfunction "GND_5") (pintype "passive"))
    )
    (net (code "85") (name "Net-(BAT-VCC)") (class "Default")
      (node (ref "BAT") (pin "1") (pinfunction "VCC_1") (pintype "passive"))
      (node (ref "D2") (pin "1") (pintype "passive"))
    )
    (net (code "86") (name "Net-(BOOT-Pad3)") (class "Default")
      (node (ref "BOOT") (pin "3") (pinfunction "3_3") (pintype "passive"))
      (node (ref "R10") (pin "2") (pintype "passive"))
    )
    (net (code "87") (name "Net-(BOOT-Pad4)") (class "Default")
      (node (ref "BOOT") (pin "4") (pinfunction "4_4") (pintype "passive"))
      (node (ref "R11") (pin "1") (pintype "passive"))
    )
    (net (code "88") (name "Net-(D4-Pad1)") (class "Default")
      (node (ref "D4") (pin "1") (pintype "passive"))
      (node (ref "DC_IN") (pin "1") (pintype "passive"))
    )
    (net (code "89") (name "Net-(Q2-B)") (class "Default")
      (node (ref "Q2") (pin "2") (pinfunction "B_2") (pintype "passive"))
      (node (ref "R41") (pin "2") (pintype "passive"))
    )
    (net (code "90") (name "Net-(Q2-C)") (class "Default")
      (node (ref "D7") (pin "2") (pintype "passive"))
      (node (ref "Q2") (pin "3") (pinfunction "C_3") (pintype "passive"))
      (node (ref "R40") (pin "1") (pintype "passive"))
    )
    (net (code "91") (name "Net-(Q2-E)") (class "Default")
      (node (ref "Q2") (pin "1") (pinfunction "E_1") (pintype "passive"))
      (node (ref "R42") (pin "1") (pintype "passive"))
      (node (ref "U12") (pin "14") (pinfunction "RTS#_14") (pintype "passive"))
    )
    (net (code "92") (name "Net-(Q3-B)") (class "Default")
      (node (ref "Q3") (pin "2") (pinfunction "B_2") (pintype "passive"))
      (node (ref "R42") (pin "2") (pintype "passive"))
    )
    (net (code "93") (name "Net-(Q3-C)") (class "Default")
      (node (ref "Q3") (pin "3") (pinfunction "C_3") (pintype "passive"))
      (node (ref "R43") (pin "2") (pintype "passive"))
    )
    (net (code "94") (name "Net-(U1-OSC_IN)") (class "Default")
      (node (ref "22") (pin "2") (pintype "passive"))
      (node (ref "R1") (pin "2") (pintype "passive"))
      (node (ref "U1") (pin "23") (pinfunction "OSC_IN_23") (pintype "passive"))
      (node (ref "Y2") (pin "1") (pinfunction "OSC1_1") (pintype "passive"))
    )
    (net (code "95") (name "Net-(U1-OSC_OUT)") (class "Default")
      (node (ref "C6") (pin "2") (pintype "passive"))
      (node (ref "R1") (pin "1") (pintype "passive"))
      (node (ref "U1") (pin "24") (pinfunction "OSC_OUT_24") (pintype "passive"))
      (node (ref "Y2") (pin "2") (pinfunction "OSC2_2") (pintype "passive"))
    )
    (net (code "96") (name "Net-(U1-PC14-OSC32_IN)") (class "Default")
      (node (ref "C3") (pin "2") (pintype "passive"))
      (node (ref "U1") (pin "8") (pinfunction "PC14-OSC32_IN_8") (pintype "passive"))
      (node (ref "Y1") (pin "1") (pinfunction "OSC1_1") (pintype "passive"))
    )
    (net (code "97") (name "Net-(U1-PC15-OSC32_OUT)") (class "Default")
      (node (ref "C4") (pin "2") (pintype "passive"))
      (node (ref "U1") (pin "9") (pinfunction "PC15-OSC32_OUT_9") (pintype "passive"))
      (node (ref "Y1") (pin "2") (pinfunction "OSC2_2") (pintype "passive"))
    )
    (net (code "98") (name "Net-(U1-VBAT)") (class "Default")
      (node (ref "C5") (pin "2") (pintype "passive"))
      (node (ref "D1") (pin "2") (pintype "passive"))
      (node (ref "D2") (pin "2") (pintype "passive"))
      (node (ref "U1") (pin "6") (pinfunction "VBAT_6") (pintype "passive"))
    )
    (net (code "99") (name "Net-(U11-BST)") (class "Default")
      (node (ref "C32") (pin "1") (pintype "passive"))
      (node (ref "U11") (pin "1") (pinfunction "BST_1") (pintype "passive"))
    )
    (net (code "100") (name "Net-(U11-EN)") (class "Default")
      (node (ref "R38") (pin "2") (pintype "passive"))
      (node (ref "U11") (pin "4") (pinfunction "EN_4") (pintype "passive"))
    )
    (net (code "101") (name "Net-(U11-FB)") (class "Default")
      (node (ref "R37") (pin "1") (pintype "passive"))
      (node (ref "R39") (pin "1") (pintype "passive"))
      (node (ref "U11") (pin "3") (pinfunction "FB_3") (pintype "passive"))
    )
    (net (code "102") (name "Net-(U11-IN)") (class "Default")
      (node (ref "C38") (pin "1") (pintype "passive"))
      (node (ref "C39") (pin "1") (pintype "passive"))
      (node (ref "D4") (pin "2") (pintype "passive"))
      (node (ref "R38") (pin "1") (pintype "passive"))
      (node (ref "U11") (pin "5") (pinfunction "IN_5") (pintype "passive"))
    )
    (net (code "103") (name "Net-(U11-SW)") (class "Default")
      (node (ref "C32") (pin "2") (pintype "passive"))
      (node (ref "D3") (pin "2") (pintype "passive"))
      (node (ref "L1") (pin "2") (pinfunction "2_2") (pintype "passive"))
      (node (ref "U11") (pin "6") (pinfunction "SW_6") (pintype "passive"))
    )
    (net (code "104") (name "Net-(U12-DTR#)") (class "Default")
      (node (ref "R41") (pin "1") (pintype "passive"))
      (node (ref "U12") (pin "13") (pinfunction "DTR#_13") (pintype "passive"))
    )
    (net (code "105") (name "Net-(U12-V3)") (class "Default")
      (node (ref "C42") (pin "2") (pintype "passive"))
      (node (ref "U12") (pin "4") (pinfunction "V3_4") (pintype "passive"))
    )
    (net (code "106") (name "Net-(U12-XI)") (class "Default")
      (node (ref "C44") (pin "2") (pintype "passive"))
      (node (ref "U12") (pin "7") (pinfunction "XI_7") (pintype "passive"))
      (node (ref "Y3") (pin "1") (pinfunction "OSC1_1") (pintype "passive"))
    )
    (net (code "107") (name "Net-(U12-XO)") (class "Default")
      (node (ref "C43") (pin "2") (pintype "passive"))
      (node (ref "U12") (pin "8") (pinfunction "XO_8") (pintype "passive"))
      (node (ref "Y3") (pin "2") (pinfunction "OSC2_2") (pintype "passive"))
    )
    (net (code "108") (name "VBTN") (class "Default")
      (node (ref "C36") (pin "2") (pintype "passive"))
      (node (ref "C37") (pin "1") (pinfunction "VCC_1") (pintype "passive"))
      (node (ref "F1") (pin "2") (pintype "passive"))
      (node (ref "K1") (pin "5") (pinfunction "TAP2_5") (pintype "passive"))
      (node (ref "L1") (pin "1") (pinfunction "1_1") (pintype "passive"))
      (node (ref "R39") (pin "2") (pintype "passive"))
    )
    (net (code "109") (name "VCC") (class "Default")
      (node (ref "C40") (pin "1") (pintype "passive"))
      (node (ref "C41") (pin "1") (pintype "passive"))
      (node (ref "U12") (pin "16") (pinfunction "VCC_16") (pintype "passive"))
    )
    (net (code "110") (name "VCC3.3") (class "Default")
      (node (ref "2.8'LCD") (pin "24") (pinfunction "VDD3.3_24") (pintype "passive"))
      (node (ref "2.8'LCD") (pin "25") (pinfunction "VDD3.3_25") (pintype "passive"))
      (node (ref "BOOT") (pin "1") (pinfunction "1_1") (pintype "passive"))
      (node (ref "BOOT") (pin "2") (pinfunction "2_2") (pintype "passive"))
      (node (ref "C1") (pin "1") (pintype "passive"))
      (node (ref "C33") (pin "2") (pintype "passive"))
      (node (ref "C34") (pin "1") (pinfunction "VCC_1") (pintype "passive"))
      (node (ref "Q3") (pin "1") (pinfunction "E_1") (pintype "passive"))
      (node (ref "R2") (pin "1") (pintype "passive"))
      (node (ref "R3") (pin "2") (pintype "passive"))
      (node (ref "R40") (pin "2") (pintype "passive"))
      (node (ref "R7") (pin "1") (pintype "passive"))
      (node (ref "R8") (pin "1") (pintype "passive"))
      (node (ref "U10") (pin "2") (pinfunction "OUT_2") (pintype "passive"))
      (node (ref "U10") (pin "4") (pinfunction "OUT_4") (pintype "passive"))
    )
    (net (code "111") (name "VCC3.3M") (class "Default")
      (node (ref "C11") (pin "2") (pintype "passive"))
      (node (ref "C12") (pin "2") (pintype "passive"))
      (node (ref "C13") (pin "2") (pintype "passive"))
      (node (ref "C14") (pin "2") (pintype "passive"))
      (node (ref "C15") (pin "2") (pintype "passive"))
      (node (ref "C16") (pin "2") (pintype "passive"))
      (node (ref "C17") (pin "2") (pintype "passive"))
      (node (ref "C18") (pin "2") (pintype "passive"))
      (node (ref "C19") (pin "2") (pintype "passive"))
      (node (ref "C20") (pin "2") (pintype "passive"))
      (node (ref "C21") (pin "2") (pintype "passive"))
      (node (ref "D1") (pin "1") (pintype "passive"))
      (node (ref "R7") (pin "2") (pintype "passive"))
      (node (ref "R8") (pin "2") (pintype "passive"))
      (node (ref "U1") (pin "108") (pinfunction "VDD_108") (pintype "passive"))
      (node (ref "U1") (pin "121") (pinfunction "VDD_121") (pintype "passive"))
      (node (ref "U1") (pin "131") (pinfunction "VDD_131") (pintype "passive"))
      (node (ref "U1") (pin "144") (pinfunction "VDD_144") (pintype "passive"))
      (node (ref "U1") (pin "17") (pinfunction "VDD_17") (pintype "passive"))
      (node (ref "U1") (pin "39") (pinfunction "VDD_39") (pintype "passive"))
      (node (ref "U1") (pin "52") (pinfunction "VDD_52") (pintype "passive"))
      (node (ref "U1") (pin "62") (pinfunction "VDD_62") (pintype "passive"))
      (node (ref "U1") (pin "72") (pinfunction "VDD_72") (pintype "passive"))
      (node (ref "U1") (pin "84") (pinfunction "VDD_84") (pintype "passive"))
      (node (ref "U1") (pin "95") (pinfunction "VDD_95") (pintype "passive"))
    )
    (net (code "112") (name "VCC5") (class "Default")
      (node (ref "2.8'LCD") (pin "28") (pinfunction "BL_VDD_28") (pintype "passive"))
      (node (ref "C101") (pin "2") (pintype "passive"))
      (node (ref "C102") (pin "2") (pintype "passive"))
      (node (ref "C103") (pin "2") (pintype "passive"))
      (node (ref "C104") (pin "2") (pintype "passive"))
      (node (ref "C2") (pin "1") (pintype "passive"))
      (node (ref "C35") (pin "2") (pintype "passive"))
      (node (ref "J11") (pin "6") (pinfunction "6_6") (pintype "passive"))
      (node (ref "J11") (pin "7") (pinfunction "7_7") (pintype "passive"))
      (node (ref "J12") (pin "6") (pinfunction "6_6") (pintype "passive"))
      (node (ref "J12") (pin "7") (pinfunction "7_7") (pintype "passive"))
      (node (ref "J13") (pin "6") (pinfunction "6_6") (pintype "passive"))
      (node (ref "J13") (pin "7") (pinfunction "7_7") (pintype "passive"))
      (node (ref "J14") (pin "6") (pinfunction "6_6") (pintype "passive"))
      (node (ref "J14") (pin "7") (pinfunction "7_7") (pintype "passive"))
      (node (ref "K1") (pin "6") (pinfunction "I/O2_6") (pintype "passive"))
      (node (ref "U10") (pin "3") (pinfunction "IN_3") (pintype "passive"))
      (node (ref "U21") (pin "9") (pinfunction "9_9") (pintype "passive"))
      (node (ref "U22") (pin "9") (pinfunction "9_9") (pintype "passive"))
      (node (ref "U23") (pin "9") (pinfunction "9_9") (pintype "passive"))
      (node (ref "U24") (pin "9") (pinfunction "9_9") (pintype "passive"))
    )
    (net (code "113") (name "VDDA") (class "Default")
      (node (ref "C8") (pin "2") (pintype "passive"))
      (node (ref "C9") (pin "2") (pintype "passive"))
      (node (ref "R3") (pin "1") (pintype "passive"))
      (node (ref "U1") (pin "32") (pinfunction "Vref+_32") (pintype "passive"))
      (node (ref "U1") (pin "33") (pinfunction "VDDA_33") (pintype "passive"))
    )
    (net (code "114") (name "VM1") (class "Default")
      (node (ref "J11") (pin "5") (pinfunction "5_5") (pintype "passive"))
      (node (ref "J21") (pin "5") (pinfunction "5_5") (pintype "passive"))
    )
    (net (code "115") (name "VM2") (class "Default")
      (node (ref "J12") (pin "5") (pinfunction "5_5") (pintype "passive"))
      (node (ref "J22") (pin "5") (pinfunction "5_5") (pintype "passive"))
    )
    (net (code "116") (name "VM3") (class "Default")
      (node (ref "J13") (pin "5") (pinfunction "5_5") (pintype "passive"))
      (node (ref "J23") (pin "5") (pinfunction "5_5") (pintype "passive"))
    )
    (net (code "117") (name "VM4") (class "Default")
      (node (ref "J14") (pin "5") (pinfunction "5_5") (pintype "passive"))
      (node (ref "J24") (pin "5") (pinfunction "5_5") (pintype "passive"))
    )
    (net (code "118") (name "VUSB") (class "Default")
      (node (ref "F1") (pin "1") (pintype "passive"))
      (node (ref "USB_232") (pin "1") (pinfunction "VCC_1") (pintype "passive"))
    )
    (net (code "119") (name "unconnected-(2.8'LCD-MO-Pad32)") (class "Default")
      (node (ref "2.8'LCD") (pin "32") (pinfunction "MO_32") (pintype "passive"))
    )
    (net (code "120") (name "unconnected-(K1-I{slash}O1-Pad1)") (class "Default")
      (node (ref "K1") (pin "1") (pinfunction "I/O1_1") (pintype "passive"))
    )
    (net (code "121") (name "unconnected-(K1-I{slash}O1-Pad3)") (class "Default")
      (node (ref "K1") (pin "3") (pinfunction "I/O1_3") (pintype "passive"))
    )
    (net (code "122") (name "unconnected-(K1-I{slash}O2-Pad4)") (class "Default")
      (node (ref "K1") (pin "4") (pinfunction "I/O2_4") (pintype "passive"))
    )
    (net (code "123") (name "unconnected-(K1-TAP1-Pad2)") (class "Default")
      (node (ref "K1") (pin "2") (pinfunction "TAP1_2") (pintype "passive"))
    )
    (net (code "124") (name "unconnected-(P1-Pad1)") (class "Default")
      (node (ref "P1") (pin "1") (pinfunction "1_1") (pintype "passive"))
    )
    (net (code "125") (name "unconnected-(P1-Pad2)") (class "Default")
      (node (ref "P1") (pin "2") (pinfunction "2_2") (pintype "passive"))
    )
    (net (code "126") (name "unconnected-(P1-Pad3)") (class "Default")
      (node (ref "P1") (pin "3") (pinfunction "3_3") (pintype "passive"))
    )
    (net (code "127") (name "unconnected-(P1-Pad4)") (class "Default")
      (node (ref "P1") (pin "4") (pinfunction "4_4") (pintype "passive"))
    )
    (net (code "128") (name "unconnected-(P1-Pad5)") (class "Default")
      (node (ref "P1") (pin "5") (pinfunction "5_5") (pintype "passive"))
    )
    (net (code "129") (name "unconnected-(P1-Pad6)") (class "Default")
      (node (ref "P1") (pin "6") (pinfunction "6_6") (pintype "passive"))
    )
    (net (code "130") (name "unconnected-(P1-Pad7)") (class "Default")
      (node (ref "P1") (pin "7") (pinfunction "7_7") (pintype "passive"))
    )
    (net (code "131") (name "unconnected-(P1-Pad8)") (class "Default")
      (node (ref "P1") (pin "8") (pinfunction "8_8") (pintype "passive"))
    )
    (net (code "132") (name "unconnected-(P1-Pad9)") (class "Default")
      (node (ref "P1") (pin "9") (pinfunction "9_9") (pintype "passive"))
    )
    (net (code "133") (name "unconnected-(P1-Pad10)") (class "Default")
      (node (ref "P1") (pin "10") (pinfunction "10_10") (pintype "passive"))
    )
    (net (code "134") (name "unconnected-(P1-Pad19)") (class "Default")
      (node (ref "P1") (pin "19") (pinfunction "19_19") (pintype "passive"))
    )
    (net (code "135") (name "unconnected-(P1-Pad20)") (class "Default")
      (node (ref "P1") (pin "20") (pinfunction "20_20") (pintype "passive"))
    )
    (net (code "136") (name "unconnected-(P1-Pad25)") (class "Default")
      (node (ref "P1") (pin "25") (pinfunction "25_25") (pintype "passive"))
    )
    (net (code "137") (name "unconnected-(P1-Pad26)") (class "Default")
      (node (ref "P1") (pin "26") (pinfunction "26_26") (pintype "passive"))
    )
    (net (code "138") (name "unconnected-(P1-Pad31)") (class "Default")
      (node (ref "P1") (pin "31") (pinfunction "31_31") (pintype "passive"))
    )
    (net (code "139") (name "unconnected-(P1-Pad32)") (class "Default")
      (node (ref "P1") (pin "32") (pinfunction "32_32") (pintype "passive"))
    )
    (net (code "140") (name "unconnected-(P1-Pad33)") (class "Default")
      (node (ref "P1") (pin "33") (pinfunction "33_33") (pintype "passive"))
    )
    (net (code "141") (name "unconnected-(P1-Pad34)") (class "Default")
      (node (ref "P1") (pin "34") (pinfunction "34_34") (pintype "passive"))
    )
    (net (code "142") (name "unconnected-(P1-Pad35)") (class "Default")
      (node (ref "P1") (pin "35") (pinfunction "35_35") (pintype "passive"))
    )
    (net (code "143") (name "unconnected-(P1-Pad36)") (class "Default")
      (node (ref "P1") (pin "36") (pinfunction "36_36") (pintype "passive"))
    )
    (net (code "144") (name "unconnected-(P1-Pad37)") (class "Default")
      (node (ref "P1") (pin "37") (pinfunction "37_37") (pintype "passive"))
    )
    (net (code "145") (name "unconnected-(P1-Pad38)") (class "Default")
      (node (ref "P1") (pin "38") (pinfunction "38_38") (pintype "passive"))
    )
    (net (code "146") (name "unconnected-(P1-Pad39)") (class "Default")
      (node (ref "P1") (pin "39") (pinfunction "39_39") (pintype "passive"))
    )
    (net (code "147") (name "unconnected-(P1-Pad40)") (class "Default")
      (node (ref "P1") (pin "40") (pinfunction "40_40") (pintype "passive"))
    )
    (net (code "148") (name "unconnected-(P1-Pad41)") (class "Default")
      (node (ref "P1") (pin "41") (pinfunction "41_41") (pintype "passive"))
    )
    (net (code "149") (name "unconnected-(P1-Pad42)") (class "Default")
      (node (ref "P1") (pin "42") (pinfunction "42_42") (pintype "passive"))
    )
    (net (code "150") (name "unconnected-(P1-Pad43)") (class "Default")
      (node (ref "P1") (pin "43") (pinfunction "43_43") (pintype "passive"))
    )
    (net (code "151") (name "unconnected-(P1-Pad44)") (class "Default")
      (node (ref "P1") (pin "44") (pinfunction "44_44") (pintype "passive"))
    )
    (net (code "152") (name "unconnected-(P1-Pad45)") (class "Default")
      (node (ref "P1") (pin "45") (pinfunction "45_45") (pintype "passive"))
    )
    (net (code "153") (name "unconnected-(P1-Pad46)") (class "Default")
      (node (ref "P1") (pin "46") (pinfunction "46_46") (pintype "passive"))
    )
    (net (code "154") (name "unconnected-(P1-Pad47)") (class "Default")
      (node (ref "P1") (pin "47") (pinfunction "47_47") (pintype "passive"))
    )
    (net (code "155") (name "unconnected-(P1-Pad48)") (class "Default")
      (node (ref "P1") (pin "48") (pinfunction "48_48") (pintype "passive"))
    )
    (net (code "156") (name "unconnected-(P1-Pad49)") (class "Default")
      (node (ref "P1") (pin "49") (pinfunction "49_49") (pintype "passive"))
    )
    (net (code "157") (name "unconnected-(P1-Pad50)") (class "Default")
      (node (ref "P1") (pin "50") (pinfunction "50_50") (pintype "passive"))
    )
    (net (code "158") (name "unconnected-(P1-Pad51)") (class "Default")
      (node (ref "P1") (pin "51") (pinfunction "51_51") (pintype "passive"))
    )
    (net (code "159") (name "unconnected-(P1-Pad52)") (class "Default")
      (node (ref "P1") (pin "52") (pinfunction "52_52") (pintype "passive"))
    )
    (net (code "160") (name "unconnected-(P1-Pad53)") (class "Default")
      (node (ref "P1") (pin "53") (pinfunction "53_53") (pintype "passive"))
    )
    (net (code "161") (name "unconnected-(P1-Pad54)") (class "Default")
      (node (ref "P1") (pin "54") (pinfunction "54_54") (pintype "passive"))
    )
    (net (code "162") (name "unconnected-(U1-NC-Pad106)") (class "Default")
      (node (ref "U1") (pin "106") (pinfunction "NC_106") (pintype "passive"))
    )
    (net (code "163") (name "unconnected-(U1-PA0-WKUP{slash}USART2_CTS{slash}ADC123_IN0{slash}TIM5_CH1{slash}TIM2_CH1_ETR{slash}TIM8_ETR-Pad34)") (class "Default")
      (node (ref "U1") (pin "34") (pinfunction "PA0-WKUP/USART2_CTS/ADC123_IN0/TIM5_CH1/TIM2_CH1_ETR/TIM8_ETR_34") (pintype "passive"))
    )
    (net (code "164") (name "unconnected-(U1-PA1{slash}USART2_RTS{slash}ADC123_IN1{slash}TIM5_CH2{slash}TIM2_CH2-Pad35)") (class "Default")
      (node (ref "U1") (pin "35") (pinfunction "PA1/USART2_RTS/ADC123_IN1/TIM5_CH2/TIM2_CH2_35") (pintype "passive"))
    )
    (net (code "165") (name "unconnected-(U1-PA2{slash}USART2_TX{slash}ADC123_IN2{slash}TIM5_CH3{slash}TIM2_CH3-Pad36)") (class "Default")
      (node (ref "U1") (pin "36") (pinfunction "PA2/USART2_TX/ADC123_IN2/TIM5_CH3/TIM2_CH3_36") (pintype "passive"))
    )
    (net (code "166") (name "unconnected-(U1-PA3{slash}USART2_RX{slash}ADC123_IN3{slash}TIM5_CH4{slash}TIM2_CH4-Pad37)") (class "Default")
      (node (ref "U1") (pin "37") (pinfunction "PA3/USART2_RX/ADC123_IN3/TIM5_CH4/TIM2_CH4_37") (pintype "passive"))
    )
    (net (code "167") (name "unconnected-(U1-PA8{slash}USART1_CK{slash}TIM1_CH1{slash}MCO-Pad100)") (class "Default")
      (node (ref "U1") (pin "100") (pinfunction "PA8/USART1_CK/TIM1_CH1/MCO_100") (pintype "passive"))
    )
    (net (code "168") (name "unconnected-(U1-PA11{slash}USART1_CTS{slash}CAN_RX{slash}TIM1_CH4{slash}USBDM-Pad103)") (class "Default")
      (node (ref "U1") (pin "103") (pinfunction "PA11/USART1_CTS/CAN_RX/TIM1_CH4/USBDM_103") (pintype "passive"))
    )
    (net (code "169") (name "unconnected-(U1-PA12{slash}USART1_RTS{slash}CAN_TX{slash}TIM1_ETR{slash}USBDP-Pad104)") (class "Default")
      (node (ref "U1") (pin "104") (pinfunction "PA12/USART1_RTS/CAN_TX/TIM1_ETR/USBDP_104") (pintype "passive"))
    )
    (net (code "170") (name "unconnected-(U1-PA13{slash}JTMS_SWDIO-Pad105)") (class "Default")
      (node (ref "U1") (pin "105") (pinfunction "PA13/JTMS_SWDIO_105") (pintype "passive"))
    )
    (net (code "171") (name "unconnected-(U1-PA14{slash}JTCK_SWCLK-Pad109)") (class "Default")
      (node (ref "U1") (pin "109") (pinfunction "PA14/JTCK_SWCLK_109") (pintype "passive"))
    )
    (net (code "172") (name "unconnected-(U1-PA15{slash}JTDI{slash}SPI3_NSS{slash}I2S3_WS-Pad110)") (class "Default")
      (node (ref "U1") (pin "110") (pinfunction "PA15/JTDI/SPI3_NSS/I2S3_WS_110") (pintype "passive"))
    )
    (net (code "173") (name "unconnected-(U1-PB3{slash}JTDO{slash}TRACESWO{slash}SPI3_SCK{slash}I2S3_CK-Pad133)") (class "Default")
      (node (ref "U1") (pin "133") (pinfunction "PB3/JTDO/TRACESWO/SPI3_SCK/I2S3_CK_133") (pintype "passive"))
    )
    (net (code "174") (name "unconnected-(U1-PB4{slash}JNTRST{slash}SPI3_MISO-Pad134)") (class "Default")
      (node (ref "U1") (pin "134") (pinfunction "PB4/JNTRST/SPI3_MISO_134") (pintype "passive"))
    )
    (net (code "175") (name "unconnected-(U1-PB5{slash}I2C1_SMBAI{slash}SPI3_MOSI{slash}I2S3_SD-Pad135)") (class "Default")
      (node (ref "U1") (pin "135") (pinfunction "PB5/I2C1_SMBAI/SPI3_MOSI/I2S3_SD_135") (pintype "passive"))
    )
    (net (code "176") (name "unconnected-(U1-PB6{slash}I2C1_SCL{slash}TIM4_CH1-Pad136)") (class "Default")
      (node (ref "U1") (pin "136") (pinfunction "PB6/I2C1_SCL/TIM4_CH1_136") (pintype "passive"))
    )
    (net (code "177") (name "unconnected-(U1-PB7{slash}I2C1_SDA{slash}FSMC_NADV{slash}TIM4_CH2-Pad137)") (class "Default")
      (node (ref "U1") (pin "137") (pinfunction "PB7/I2C1_SDA/FSMC_NADV/TIM4_CH2_137") (pintype "passive"))
    )
    (net (code "178") (name "unconnected-(U1-PB8{slash}TIM4_CH3{slash}SDIO_D4-Pad139)") (class "Default")
      (node (ref "U1") (pin "139") (pinfunction "PB8/TIM4_CH3/SDIO_D4_139") (pintype "passive"))
    )
    (net (code "179") (name "unconnected-(U1-PB9{slash}TIM4_CH4{slash}SDIO_D5-Pad140)") (class "Default")
      (node (ref "U1") (pin "140") (pinfunction "PB9/TIM4_CH4/SDIO_D5_140") (pintype "passive"))
    )
    (net (code "180") (name "unconnected-(U1-PB10{slash}I2C2_SCL{slash}USART3_TX-Pad69)") (class "Default")
      (node (ref "U1") (pin "69") (pinfunction "PB10/I2C2_SCL/USART3_TX_69") (pintype "passive"))
    )
    (net (code "181") (name "unconnected-(U1-PB11{slash}I2C2_SDA{slash}USART3_RX-Pad70)") (class "Default")
      (node (ref "U1") (pin "70") (pinfunction "PB11/I2C2_SDA/USART3_RX_70") (pintype "passive"))
    )
    (net (code "182") (name "unconnected-(U1-PB12{slash}SPI2_NSS{slash}I2S2_WS{slash}I2C2_SMBAI{slash}USART3_CK{slash}TIM1BKIN-Pad73)") (class "Default")
      (node (ref "U1") (pin "73") (pinfunction "PB12/SPI2_NSS/I2S2_WS/I2C2_SMBAI/USART3_CK/TIM1BKIN_73") (pintype "passive"))
    )
    (net (code "183") (name "unconnected-(U1-PB13{slash}SPI2_SCK{slash}I2S2_CK{slash}USART3_CTS{slash}TIM1_CH1N-Pad74)") (class "Default")
      (node (ref "U1") (pin "74") (pinfunction "PB13/SPI2_SCK/I2S2_CK/USART3_CTS/TIM1_CH1N_74") (pintype "passive"))
    )
    (net (code "184") (name "unconnected-(U1-PB14{slash}SPI2_MISO{slash}USART3_RTS{slash}TIM1_CH2N-Pad75)") (class "Default")
      (node (ref "U1") (pin "75") (pinfunction "PB14/SPI2_MISO/USART3_RTS/TIM1_CH2N_75") (pintype "passive"))
    )
    (net (code "185") (name "unconnected-(U1-PB15{slash}SPI2_MOSI{slash}I2S2_SD{slash}TIM1_CH3N-Pad76)") (class "Default")
      (node (ref "U1") (pin "76") (pinfunction "PB15/SPI2_MOSI/I2S2_SD/TIM1_CH3N_76") (pintype "passive"))
    )
    (net (code "186") (name "unconnected-(U1-PC4{slash}ADC12_IN14-Pad44)") (class "Default")
      (node (ref "U1") (pin "44") (pinfunction "PC4/ADC12_IN14_44") (pintype "passive"))
    )
    (net (code "187") (name "unconnected-(U1-PC5{slash}ADC12_IN15-Pad45)") (class "Default")
      (node (ref "U1") (pin "45") (pinfunction "PC5/ADC12_IN15_45") (pintype "passive"))
    )
    (net (code "188") (name "unconnected-(U1-PC6{slash}I2S2_MCK{slash}TIM8_CH1{slash}SDIO_D6-Pad96)") (class "Default")
      (node (ref "U1") (pin "96") (pinfunction "PC6/I2S2_MCK/TIM8_CH1/SDIO_D6_96") (pintype "passive"))
    )
    (net (code "189") (name "unconnected-(U1-PC7{slash}I2S3_MCK{slash}TIM8_CH2{slash}SDIO_D7-Pad97)") (class "Default")
      (node (ref "U1") (pin "97") (pinfunction "PC7/I2S3_MCK/TIM8_CH2/SDIO_D7_97") (pintype "passive"))
    )
    (net (code "190") (name "unconnected-(U1-PC8{slash}TIM8_CH3{slash}SDIO_D0-Pad98)") (class "Default")
      (node (ref "U1") (pin "98") (pinfunction "PC8/TIM8_CH3/SDIO_D0_98") (pintype "passive"))
    )
    (net (code "191") (name "unconnected-(U1-PC9{slash}TIM8_CH4{slash}SDIO_D1-Pad99)") (class "Default")
      (node (ref "U1") (pin "99") (pinfunction "PC9/TIM8_CH4/SDIO_D1_99") (pintype "passive"))
    )
    (net (code "192") (name "unconnected-(U1-PC10{slash}UART4_TX{slash}SDIO_D2-Pad111)") (class "Default")
      (node (ref "U1") (pin "111") (pinfunction "PC10/UART4_TX/SDIO_D2_111") (pintype "passive"))
    )
    (net (code "193") (name "unconnected-(U1-PC11{slash}UART4_RX{slash}SDIO_D3-Pad112)") (class "Default")
      (node (ref "U1") (pin "112") (pinfunction "PC11/UART4_RX/SDIO_D3_112") (pintype "passive"))
    )
    (net (code "194") (name "unconnected-(U1-PC12{slash}UART5_TX{slash}SDIO_CK-Pad113)") (class "Default")
      (node (ref "U1") (pin "113") (pinfunction "PC12/UART5_TX/SDIO_CK_113") (pintype "passive"))
    )
    (net (code "195") (name "unconnected-(U1-PC13-TAMPER-RTC-Pad7)") (class "Default")
      (node (ref "U1") (pin "7") (pinfunction "PC13-TAMPER-RTC_7") (pintype "passive"))
    )
    (net (code "196") (name "unconnected-(U1-PD2{slash}TIM3_ETR{slash}UART5_RX{slash}SDIO_CMD-Pad116)") (class "Default")
      (node (ref "U1") (pin "116") (pinfunction "PD2/TIM3_ETR/UART5_RX/SDIO_CMD_116") (pintype "passive"))
    )
    (net (code "197") (name "unconnected-(U1-PD3{slash}FSMC_CLK-Pad117)") (class "Default")
      (node (ref "U1") (pin "117") (pinfunction "PD3/FSMC_CLK_117") (pintype "passive"))
    )
    (net (code "198") (name "unconnected-(U1-PD6{slash}FSMC_NWAIT-Pad122)") (class "Default")
      (node (ref "U1") (pin "122") (pinfunction "PD6/FSMC_NWAIT_122") (pintype "passive"))
    )
    (net (code "199") (name "unconnected-(U1-PD7{slash}FSMC_NE1{slash}FSMC_NCE2-Pad123)") (class "Default")
      (node (ref "U1") (pin "123") (pinfunction "PD7/FSMC_NE1/FSMC_NCE2_123") (pintype "passive"))
    )
    (net (code "200") (name "unconnected-(U1-PD11{slash}FSMC_A16-Pad80)") (class "Default")
      (node (ref "U1") (pin "80") (pinfunction "PD11/FSMC_A16_80") (pintype "passive"))
    )
    (net (code "201") (name "unconnected-(U1-PD12{slash}FSMC_A17-Pad81)") (class "Default")
      (node (ref "U1") (pin "81") (pinfunction "PD12/FSMC_A17_81") (pintype "passive"))
    )
    (net (code "202") (name "unconnected-(U1-PD13{slash}FSMC_A18-Pad82)") (class "Default")
      (node (ref "U1") (pin "82") (pinfunction "PD13/FSMC_A18_82") (pintype "passive"))
    )
    (net (code "203") (name "unconnected-(U1-PE0{slash}TIM4_ETR{slash}FSMC_NBL0-Pad141)") (class "Default")
      (node (ref "U1") (pin "141") (pinfunction "PE0/TIM4_ETR/FSMC_NBL0_141") (pintype "passive"))
    )
    (net (code "204") (name "unconnected-(U1-PE1{slash}FSMC_NBL1-Pad142)") (class "Default")
      (node (ref "U1") (pin "142") (pinfunction "PE1/FSMC_NBL1_142") (pintype "passive"))
    )
    (net (code "205") (name "unconnected-(U1-PE2{slash}TRACECK{slash}FSMC_A23-Pad1)") (class "Default")
      (node (ref "U1") (pin "1") (pinfunction "PE2/TRACECK/FSMC_A23_1") (pintype "passive"))
    )
    (net (code "206") (name "unconnected-(U1-PE3{slash}TRACED0{slash}FSMC_A19-Pad2)") (class "Default")
      (node (ref "U1") (pin "2") (pinfunction "PE3/TRACED0/FSMC_A19_2") (pintype "passive"))
    )
    (net (code "207") (name "unconnected-(U1-PE4{slash}TRACED1{slash}FSMC_A20-Pad3)") (class "Default")
      (node (ref "U1") (pin "3") (pinfunction "PE4/TRACED1/FSMC_A20_3") (pintype "passive"))
    )
    (net (code "208") (name "unconnected-(U1-PE5{slash}TRACED2{slash}FSMC_A21-Pad4)") (class "Default")
      (node (ref "U1") (pin "4") (pinfunction "PE5/TRACED2/FSMC_A21_4") (pintype "passive"))
    )
    (net (code "209") (name "unconnected-(U1-PE6{slash}TRACED3{slash}FSMC_A22-Pad5)") (class "Default")
      (node (ref "U1") (pin "5") (pinfunction "PE6/TRACED3/FSMC_A22_5") (pintype "passive"))
    )
    (net (code "210") (name "unconnected-(U1-PF12{slash}FSMC_A6-Pad50)") (class "Default")
      (node (ref "U1") (pin "50") (pinfunction "PF12/FSMC_A6_50") (pintype "passive"))
    )
    (net (code "211") (name "unconnected-(U1-PF13{slash}FSMC_A7-Pad53)") (class "Default")
      (node (ref "U1") (pin "53") (pinfunction "PF13/FSMC_A7_53") (pintype "passive"))
    )
    (net (code "212") (name "unconnected-(U1-PF14{slash}FSMC_A8-Pad54)") (class "Default")
      (node (ref "U1") (pin "54") (pinfunction "PF14/FSMC_A8_54") (pintype "passive"))
    )
    (net (code "213") (name "unconnected-(U1-PF15{slash}FSMC_A9-Pad55)") (class "Default")
      (node (ref "U1") (pin "55") (pinfunction "PF15/FSMC_A9_55") (pintype "passive"))
    )
    (net (code "214") (name "unconnected-(U1-PG1{slash}FSMC_A11-Pad57)") (class "Default")
      (node (ref "U1") (pin "57") (pinfunction "PG1/FSMC_A11_57") (pintype "passive"))
    )
    (net (code "215") (name "unconnected-(U1-PG2{slash}FSMC_A12-Pad87)") (class "Default")
      (node (ref "U1") (pin "87") (pinfunction "PG2/FSMC_A12_87") (pintype "passive"))
    )
    (net (code "216") (name "unconnected-(U1-PG3{slash}FSMC_A13-Pad88)") (class "Default")
      (node (ref "U1") (pin "88") (pinfunction "PG3/FSMC_A13_88") (pintype "passive"))
    )
    (net (code "217") (name "unconnected-(U1-PG4{slash}FSMC_A14-Pad89)") (class "Default")
      (node (ref "U1") (pin "89") (pinfunction "PG4/FSMC_A14_89") (pintype "passive"))
    )
    (net (code "218") (name "unconnected-(U1-PG5{slash}FSMC_A15-Pad90)") (class "Default")
      (node (ref "U1") (pin "90") (pinfunction "PG5/FSMC_A15_90") (pintype "passive"))
    )
    (net (code "219") (name "unconnected-(U1-PG6{slash}FSMC_INT2-Pad91)") (class "Default")
      (node (ref "U1") (pin "91") (pinfunction "PG6/FSMC_INT2_91") (pintype "passive"))
    )
    (net (code "220") (name "unconnected-(U1-PG7{slash}FSMC_INT3-Pad92)") (class "Default")
      (node (ref "U1") (pin "92") (pinfunction "PG7/FSMC_INT3_92") (pintype "passive"))
    )
    (net (code "221") (name "unconnected-(U1-PG8-Pad93)") (class "Default")
      (node (ref "U1") (pin "93") (pinfunction "PG8_93") (pintype "passive"))
    )
    (net (code "222") (name "unconnected-(U1-PG9{slash}FSMC_NE2{slash}FSMC_NCE3-Pad124)") (class "Default")
      (node (ref "U1") (pin "124") (pinfunction "PG9/FSMC_NE2/FSMC_NCE3_124") (pintype "passive"))
    )
    (net (code "223") (name "unconnected-(U1-PG10{slash}FSMC_NCE4_1{slash}FSMC_NE3-Pad125)") (class "Default")
      (node (ref "U1") (pin "125") (pinfunction "PG10/FSMC_NCE4_1/FSMC_NE3_125") (pintype "passive"))
    )
    (net (code "224") (name "unconnected-(U1-PG11{slash}FSMC_NCE4_2-Pad126)") (class "Default")
      (node (ref "U1") (pin "126") (pinfunction "PG11/FSMC_NCE4_2_126") (pintype "passive"))
    )
    (net (code "225") (name "unconnected-(U1-PG13{slash}FSMC_A24-Pad128)") (class "Default")
      (node (ref "U1") (pin "128") (pinfunction "PG13/FSMC_A24_128") (pintype "passive"))
    )
    (net (code "226") (name "unconnected-(U1-PG14{slash}FSMC_A25-Pad129)") (class "Default")
      (node (ref "U1") (pin "129") (pinfunction "PG14/FSMC_A25_129") (pintype "passive"))
    )
    (net (code "227") (name "unconnected-(U1-PG15-Pad132)") (class "Default")
      (node (ref "U1") (pin "132") (pinfunction "PG15_132") (pintype "passive"))
    )
    (net (code "228") (name "unconnected-(U12-CTS#-Pad9)") (class "Default")
      (node (ref "U12") (pin "9") (pinfunction "CTS#_9") (pintype "passive"))
    )
    (net (code "229") (name "unconnected-(U12-DCD#-Pad12)") (class "Default")
      (node (ref "U12") (pin "12") (pinfunction "DCD#_12") (pintype "passive"))
    )
    (net (code "230") (name "unconnected-(U12-DSR#-Pad10)") (class "Default")
      (node (ref "U12") (pin "10") (pinfunction "DSR#_10") (pintype "passive"))
    )
    (net (code "231") (name "unconnected-(U12-R232-Pad15)") (class "Default")
      (node (ref "U12") (pin "15") (pinfunction "R232_15") (pintype "passive"))
    )
    (net (code "232") (name "unconnected-(U12-RI#-Pad11)") (class "Default")
      (node (ref "U12") (pin "11") (pinfunction "RI#_11") (pintype "passive"))
    )
    (net (code "233") (name "unconnected-(U21-Pad5)") (class "Default")
      (node (ref "U21") (pin "5") (pinfunction "5_5") (pintype "passive"))
    )
    (net (code "234") (name "unconnected-(U21-Pad6)") (class "Default")
      (node (ref "U21") (pin "6") (pinfunction "6_6") (pintype "passive"))
    )
    (net (code "235") (name "unconnected-(U21-Pad7)") (class "Default")
      (node (ref "U21") (pin "7") (pinfunction "7_7") (pintype "passive"))
    )
    (net (code "236") (name "unconnected-(U21-Pad10)") (class "Default")
      (node (ref "U21") (pin "10") (pinfunction "10_10") (pintype "passive"))
    )
    (net (code "237") (name "unconnected-(U21-Pad11)") (class "Default")
      (node (ref "U21") (pin "11") (pinfunction "11_11") (pintype "passive"))
    )
    (net (code "238") (name "unconnected-(U21-Pad12)") (class "Default")
      (node (ref "U21") (pin "12") (pinfunction "12_12") (pintype "passive"))
    )
    (net (code "239") (name "unconnected-(U22-Pad5)") (class "Default")
      (node (ref "U22") (pin "5") (pinfunction "5_5") (pintype "passive"))
    )
    (net (code "240") (name "unconnected-(U22-Pad6)") (class "Default")
      (node (ref "U22") (pin "6") (pinfunction "6_6") (pintype "passive"))
    )
    (net (code "241") (name "unconnected-(U22-Pad7)") (class "Default")
      (node (ref "U22") (pin "7") (pinfunction "7_7") (pintype "passive"))
    )
    (net (code "242") (name "unconnected-(U22-Pad10)") (class "Default")
      (node (ref "U22") (pin "10") (pinfunction "10_10") (pintype "passive"))
    )
    (net (code "243") (name "unconnected-(U22-Pad11)") (class "Default")
      (node (ref "U22") (pin "11") (pinfunction "11_11") (pintype "passive"))
    )
    (net (code "244") (name "unconnected-(U22-Pad12)") (class "Default")
      (node (ref "U22") (pin "12") (pinfunction "12_12") (pintype "passive"))
    )
    (net (code "245") (name "unconnected-(U23-Pad5)") (class "Default")
      (node (ref "U23") (pin "5") (pinfunction "5_5") (pintype "passive"))
    )
    (net (code "246") (name "unconnected-(U23-Pad6)") (class "Default")
      (node (ref "U23") (pin "6") (pinfunction "6_6") (pintype "passive"))
    )
    (net (code "247") (name "unconnected-(U23-Pad7)") (class "Default")
      (node (ref "U23") (pin "7") (pinfunction "7_7") (pintype "passive"))
    )
    (net (code "248") (name "unconnected-(U23-Pad10)") (class "Default")
      (node (ref "U23") (pin "10") (pinfunction "10_10") (pintype "passive"))
    )
    (net (code "249") (name "unconnected-(U23-Pad11)") (class "Default")
      (node (ref "U23") (pin "11") (pinfunction "11_11") (pintype "passive"))
    )
    (net (code "250") (name "unconnected-(U23-Pad12)") (class "Default")
      (node (ref "U23") (pin "12") (pinfunction "12_12") (pintype "passive"))
    )
    (net (code "251") (name "unconnected-(U24-Pad5)") (class "Default")
      (node (ref "U24") (pin "5") (pinfunction "5_5") (pintype "passive"))
    )
    (net (code "252") (name "unconnected-(U24-Pad6)") (class "Default")
      (node (ref "U24") (pin "6") (pinfunction "6_6") (pintype "passive"))
    )
    (net (code "253") (name "unconnected-(U24-Pad7)") (class "Default")
      (node (ref "U24") (pin "7") (pinfunction "7_7") (pintype "passive"))
    )
    (net (code "254") (name "unconnected-(U24-Pad10)") (class "Default")
      (node (ref "U24") (pin "10") (pinfunction "10_10") (pintype "passive"))
    )
    (net (code "255") (name "unconnected-(U24-Pad11)") (class "Default")
      (node (ref "U24") (pin "11") (pinfunction "11_11") (pintype "passive"))
    )
    (net (code "256") (name "unconnected-(U24-Pad12)") (class "Default")
      (node (ref "U24") (pin "12") (pinfunction "12_12") (pintype "passive"))
    )
    (net (code "257") (name "unconnected-(USB_232-NC-Pad4)") (class "Default")
      (node (ref "USB_232") (pin "4") (pinfunction "NC_4") (pintype "passive"))
    )
  )
)
